# Switch.net
KiCad netlist of a schematic drawn in Altium Designer
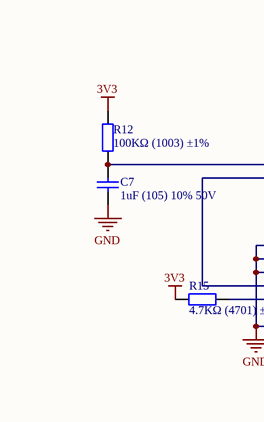
[diagram p0: Switch.SchDoc, top left]
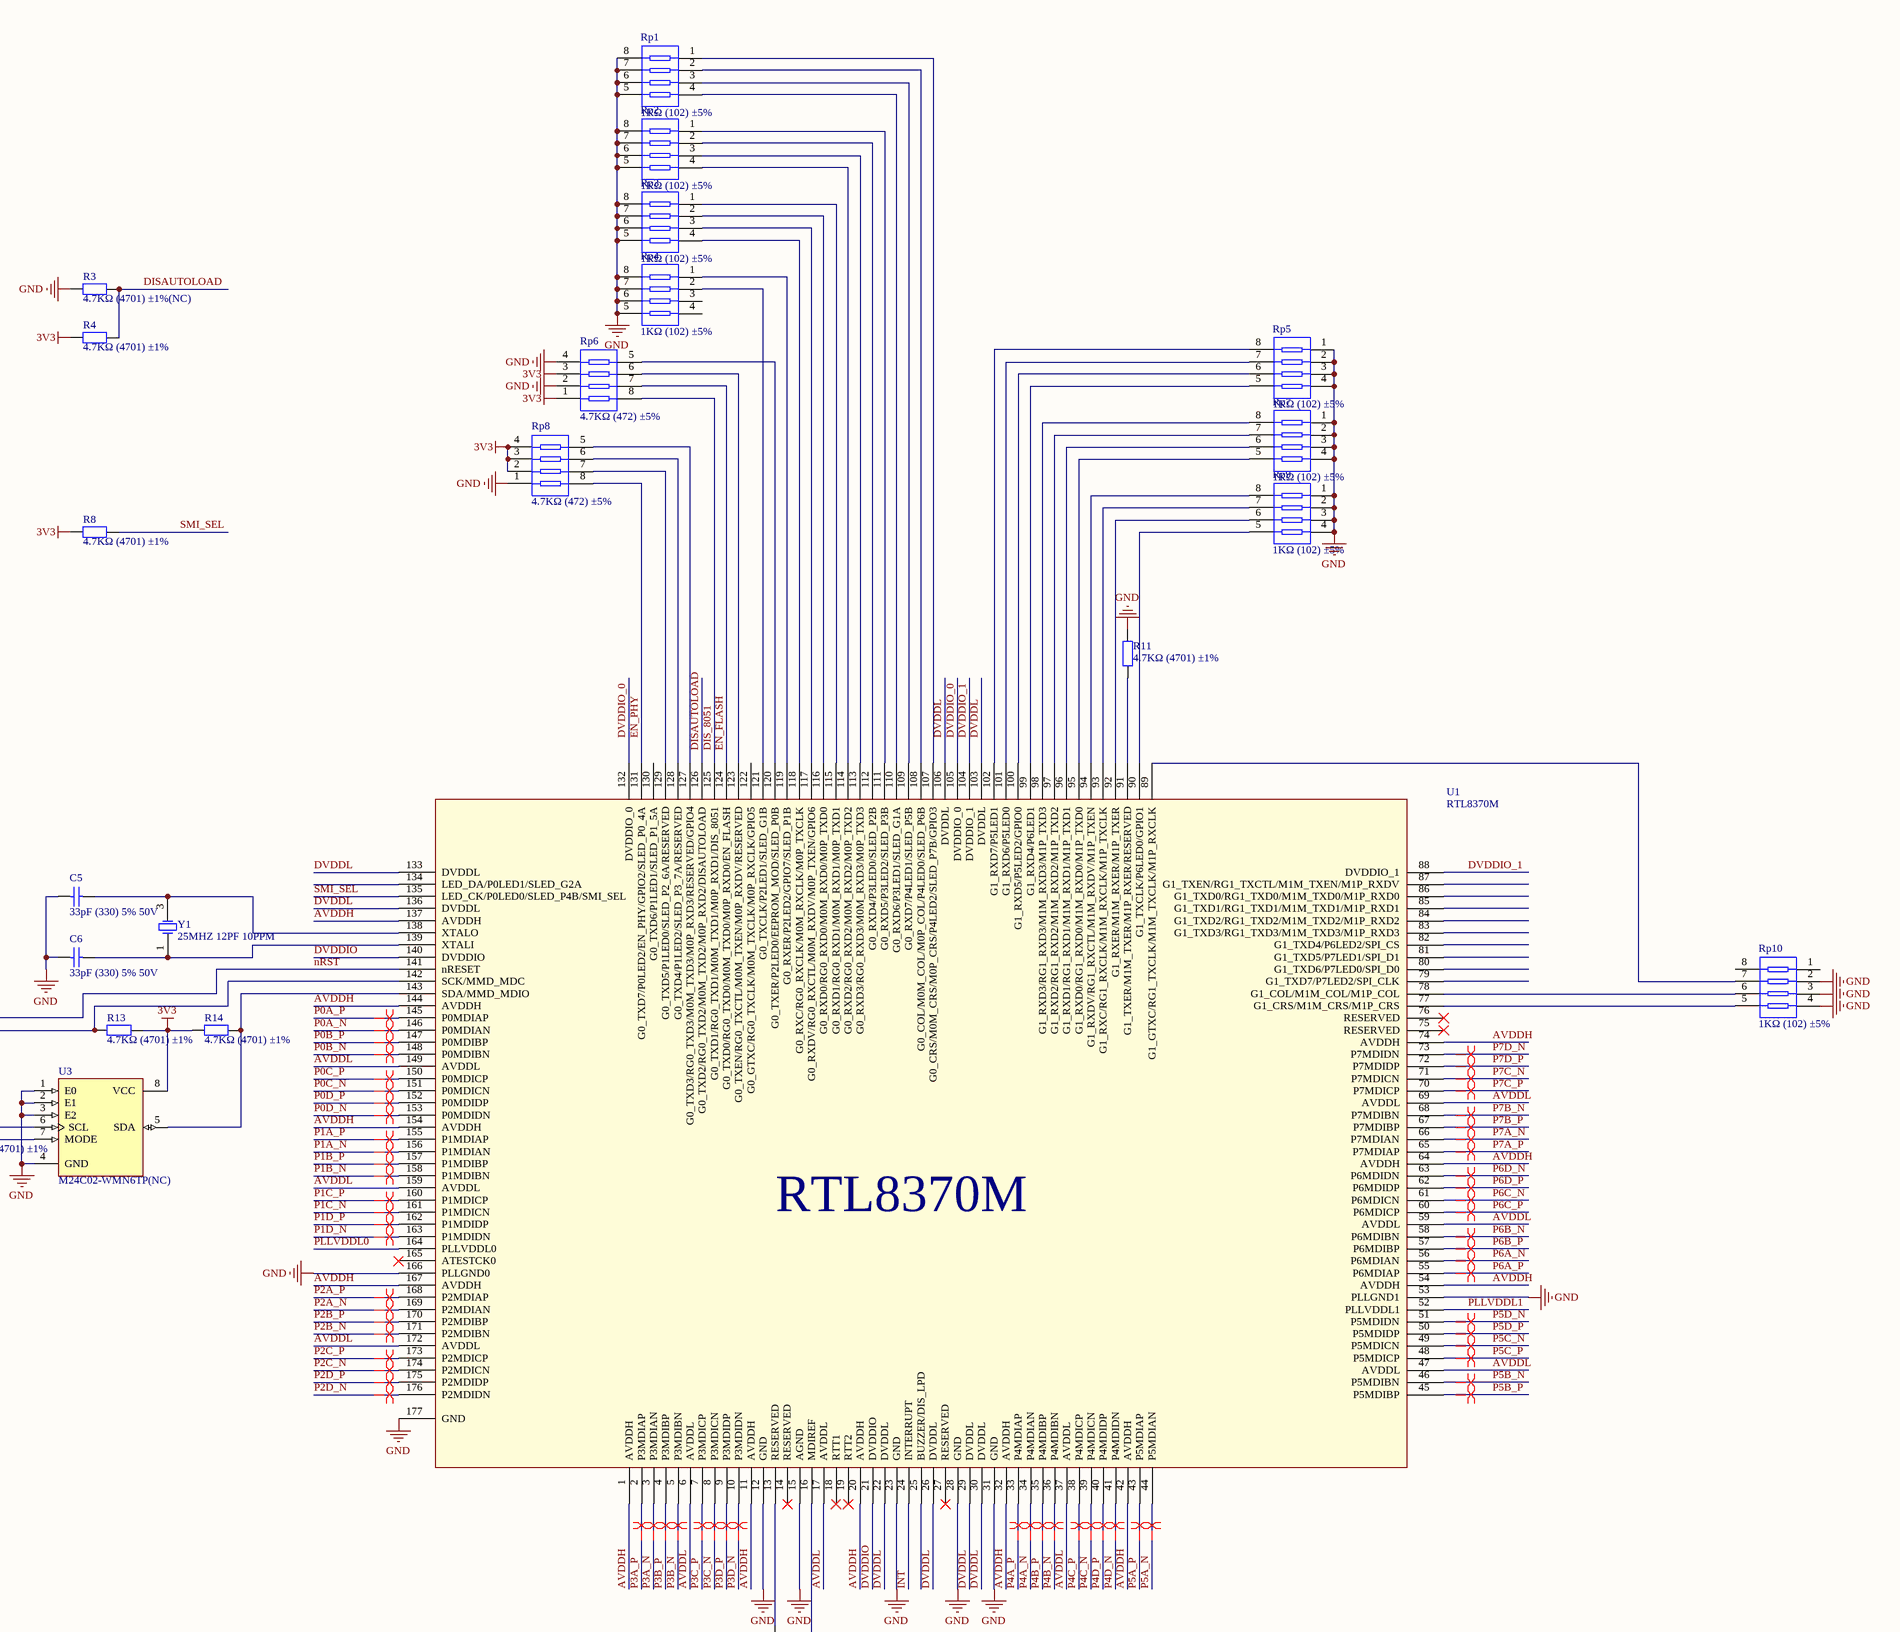
[diagram p1: Switch.SchDoc, top right]
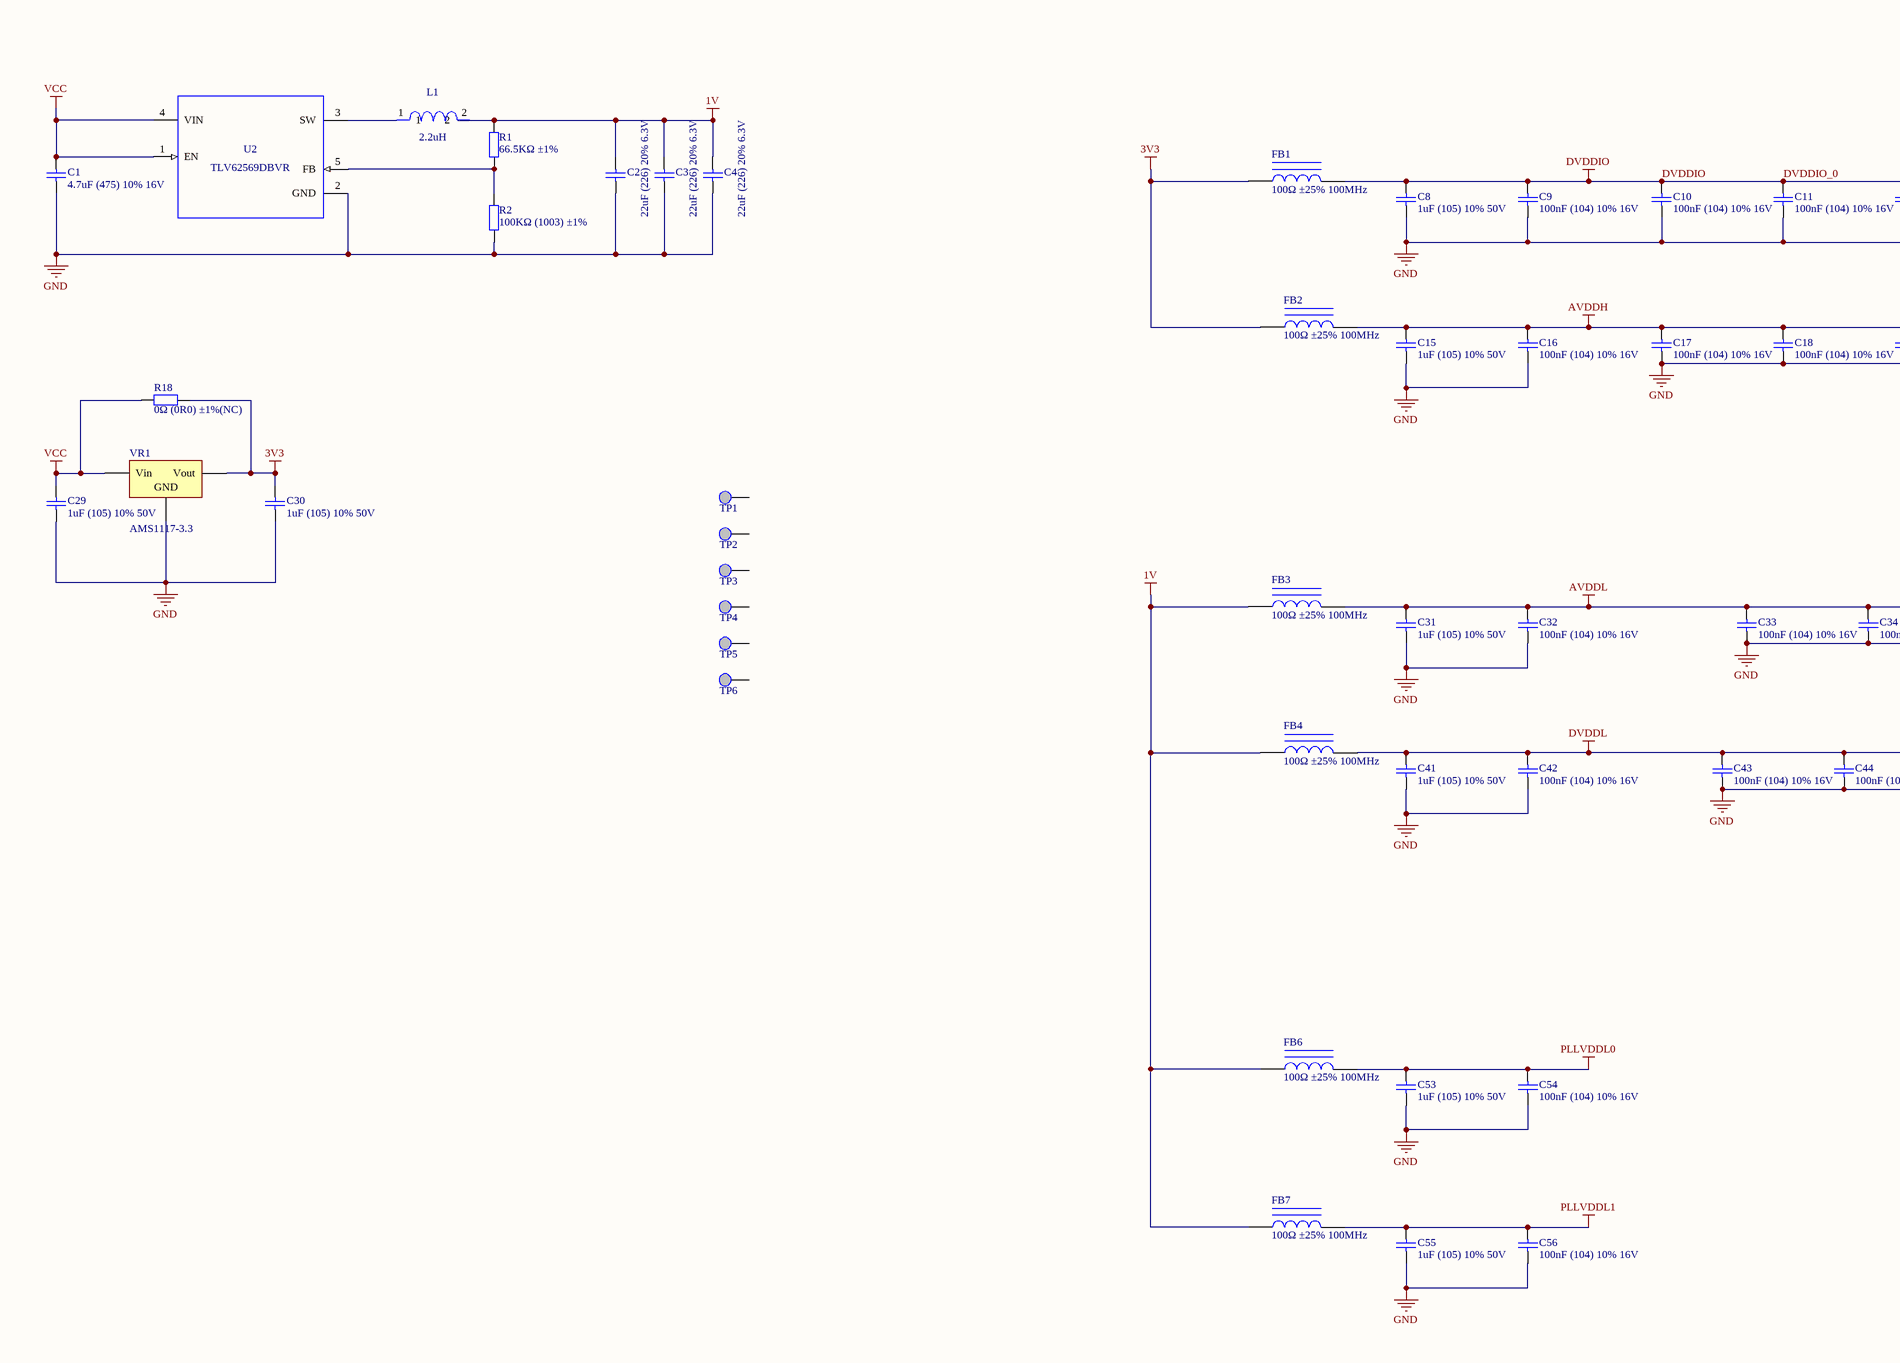
[diagram p2: Switch.SchDoc, bottom left]
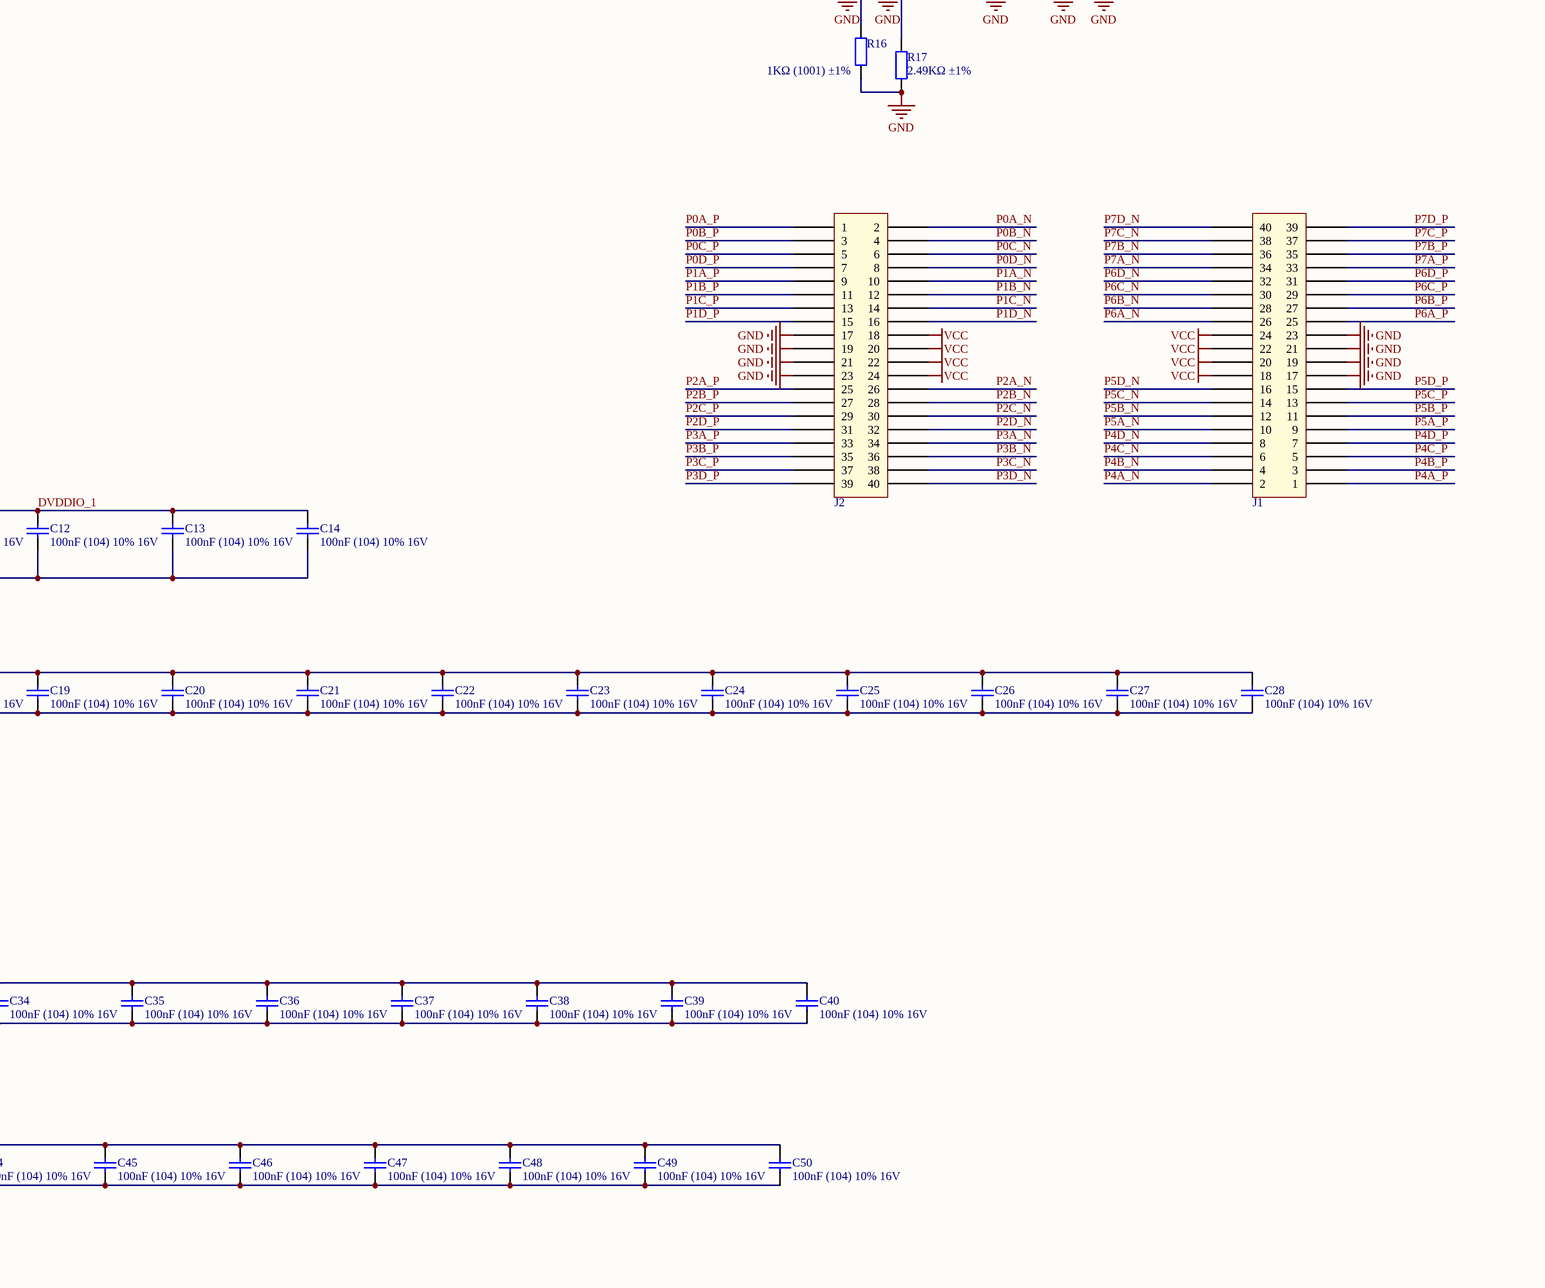
[diagram p3: Switch.SchDoc, bottom right]

(export (version "E")
  (design (tool "Eeschema 10.0.6"))
  (components
    (comp (ref "C1")
      (value "4.7uF (475) 10% 16V")
      (footprint "0603_C")
      (description "贴片电容")
      (libsource (lib "Miscellaneous Devices LC") (part "0603 4.7uF (475) 10% 16V"))
    )
    (comp (ref "C2")
      (value "22uF (226) 20% 6.3V")
      (footprint "0603_C")
      (description "贴片电容")
      (libsource (lib "Miscellaneous Devices LC") (part "0603 22uF (226) 20% 6.3V"))
    )
    (comp (ref "C3")
      (value "22uF (226) 20% 6.3V")
      (footprint "0603_C")
      (description "贴片电容")
      (libsource (lib "Miscellaneous Devices LC") (part "0603 22uF (226) 20% 6.3V"))
    )
    (comp (ref "C4")
      (value "22uF (226) 20% 6.3V")
      (footprint "0603_C")
      (description "贴片电容")
      (libsource (lib "Miscellaneous Devices LC") (part "0603 22uF (226) 20% 6.3V"))
    )
    (comp (ref "C5")
      (value "33pF (330) 5% 50V")
      (footprint "0402_C")
      (description "贴片电容")
      (libsource (lib "Miscellaneous Devices LC") (part "0402 33pF (330) 5% 50V"))
    )
    (comp (ref "C6")
      (value "33pF (330) 5% 50V")
      (footprint "0402_C")
      (description "贴片电容")
      (libsource (lib "Miscellaneous Devices LC") (part "0402 33pF (330) 5% 50V"))
    )
    (comp (ref "C7")
      (value "1uF (105) 10% 50V")
      (footprint "0603_C")
      (description "贴片电容")
      (libsource (lib "Miscellaneous Devices LC") (part "0603 1uF (105) 10% 50V"))
    )
    (comp (ref "C8")
      (value "1uF (105) 10% 50V")
      (footprint "0603_C")
      (description "贴片电容")
      (libsource (lib "Miscellaneous Devices LC") (part "0603 1uF (105) 10% 50V"))
    )
    (comp (ref "C9")
      (value "100nF (104) 10% 16V")
      (footprint "0402_C")
      (description "贴片电容")
      (libsource (lib "Miscellaneous Devices LC") (part "0402 100nF (104) 10% 16V"))
    )
    (comp (ref "C10")
      (value "100nF (104) 10% 16V")
      (footprint "0402_C")
      (description "贴片电容")
      (libsource (lib "Miscellaneous Devices LC") (part "0402 100nF (104) 10% 16V"))
    )
    (comp (ref "C11")
      (value "100nF (104) 10% 16V")
      (footprint "0402_C")
      (description "贴片电容")
      (libsource (lib "Miscellaneous Devices LC") (part "0402 100nF (104) 10% 16V"))
    )
    (comp (ref "C12")
      (value "100nF (104) 10% 16V")
      (footprint "0402_C")
      (description "贴片电容")
      (libsource (lib "Miscellaneous Devices LC") (part "0402 100nF (104) 10% 16V"))
    )
    (comp (ref "C13")
      (value "100nF (104) 10% 16V")
      (footprint "0402_C")
      (description "贴片电容")
      (libsource (lib "Miscellaneous Devices LC") (part "0402 100nF (104) 10% 16V"))
    )
    (comp (ref "C14")
      (value "100nF (104) 10% 16V")
      (footprint "0402_C")
      (description "贴片电容")
      (libsource (lib "Miscellaneous Devices LC") (part "0402 100nF (104) 10% 16V"))
    )
    (comp (ref "C15")
      (value "1uF (105) 10% 50V")
      (footprint "0603_C")
      (description "贴片电容")
      (libsource (lib "Miscellaneous Devices LC") (part "0603 1uF (105) 10% 50V"))
    )
    (comp (ref "C16")
      (value "100nF (104) 10% 16V")
      (footprint "0402_C")
      (description "贴片电容")
      (libsource (lib "Miscellaneous Devices LC") (part "0402 100nF (104) 10% 16V"))
    )
    (comp (ref "C17")
      (value "100nF (104) 10% 16V")
      (footprint "0402_C")
      (description "贴片电容")
      (libsource (lib "Miscellaneous Devices LC") (part "0402 100nF (104) 10% 16V"))
    )
    (comp (ref "C18")
      (value "100nF (104) 10% 16V")
      (footprint "0402_C")
      (description "贴片电容")
      (libsource (lib "Miscellaneous Devices LC") (part "0402 100nF (104) 10% 16V"))
    )
    (comp (ref "C19")
      (value "100nF (104) 10% 16V")
      (footprint "0402_C")
      (description "贴片电容")
      (libsource (lib "Miscellaneous Devices LC") (part "0402 100nF (104) 10% 16V"))
    )
    (comp (ref "C20")
      (value "100nF (104) 10% 16V")
      (footprint "0402_C")
      (description "贴片电容")
      (libsource (lib "Miscellaneous Devices LC") (part "0402 100nF (104) 10% 16V"))
    )
    (comp (ref "C21")
      (value "100nF (104) 10% 16V")
      (footprint "0402_C")
      (description "贴片电容")
      (libsource (lib "Miscellaneous Devices LC") (part "0402 100nF (104) 10% 16V"))
    )
    (comp (ref "C22")
      (value "100nF (104) 10% 16V")
      (footprint "0402_C")
      (description "贴片电容")
      (libsource (lib "Miscellaneous Devices LC") (part "0402 100nF (104) 10% 16V"))
    )
    (comp (ref "C23")
      (value "100nF (104) 10% 16V")
      (footprint "0402_C")
      (description "贴片电容")
      (libsource (lib "Miscellaneous Devices LC") (part "0402 100nF (104) 10% 16V"))
    )
    (comp (ref "C24")
      (value "100nF (104) 10% 16V")
      (footprint "0402_C")
      (description "贴片电容")
      (libsource (lib "Miscellaneous Devices LC") (part "0402 100nF (104) 10% 16V"))
    )
    (comp (ref "C25")
      (value "100nF (104) 10% 16V")
      (footprint "0402_C")
      (description "贴片电容")
      (libsource (lib "Miscellaneous Devices LC") (part "0402 100nF (104) 10% 16V"))
    )
    (comp (ref "C26")
      (value "100nF (104) 10% 16V")
      (footprint "0402_C")
      (description "贴片电容")
      (libsource (lib "Miscellaneous Devices LC") (part "0402 100nF (104) 10% 16V"))
    )
    (comp (ref "C27")
      (value "100nF (104) 10% 16V")
      (footprint "0402_C")
      (description "贴片电容")
      (libsource (lib "Miscellaneous Devices LC") (part "0402 100nF (104) 10% 16V"))
    )
    (comp (ref "C28")
      (value "100nF (104) 10% 16V")
      (footprint "0402_C")
      (description "贴片电容")
      (libsource (lib "Miscellaneous Devices LC") (part "0402 100nF (104) 10% 16V"))
    )
    (comp (ref "C29")
      (value "1uF (105) 10% 50V")
      (footprint "0603_C")
      (description "贴片电容")
      (libsource (lib "Miscellaneous Devices LC") (part "0603 1uF (105) 10% 50V"))
    )
    (comp (ref "C30")
      (value "1uF (105) 10% 50V")
      (footprint "0603_C")
      (description "贴片电容")
      (libsource (lib "Miscellaneous Devices LC") (part "0603 1uF (105) 10% 50V"))
    )
    (comp (ref "C31")
      (value "1uF (105) 10% 50V")
      (footprint "0603_C")
      (description "贴片电容")
      (libsource (lib "Miscellaneous Devices LC") (part "0603 1uF (105) 10% 50V"))
    )
    (comp (ref "C32")
      (value "100nF (104) 10% 16V")
      (footprint "0402_C")
      (description "贴片电容")
      (libsource (lib "Miscellaneous Devices LC") (part "0402 100nF (104) 10% 16V"))
    )
    (comp (ref "C33")
      (value "100nF (104) 10% 16V")
      (footprint "0402_C")
      (description "贴片电容")
      (libsource (lib "Miscellaneous Devices LC") (part "0402 100nF (104) 10% 16V"))
    )
    (comp (ref "C34")
      (value "100nF (104) 10% 16V")
      (footprint "0402_C")
      (description "贴片电容")
      (libsource (lib "Miscellaneous Devices LC") (part "0402 100nF (104) 10% 16V"))
    )
    (comp (ref "C35")
      (value "100nF (104) 10% 16V")
      (footprint "0402_C")
      (description "贴片电容")
      (libsource (lib "Miscellaneous Devices LC") (part "0402 100nF (104) 10% 16V"))
    )
    (comp (ref "C36")
      (value "100nF (104) 10% 16V")
      (footprint "0402_C")
      (description "贴片电容")
      (libsource (lib "Miscellaneous Devices LC") (part "0402 100nF (104) 10% 16V"))
    )
    (comp (ref "C37")
      (value "100nF (104) 10% 16V")
      (footprint "0402_C")
      (description "贴片电容")
      (libsource (lib "Miscellaneous Devices LC") (part "0402 100nF (104) 10% 16V"))
    )
    (comp (ref "C38")
      (value "100nF (104) 10% 16V")
      (footprint "0402_C")
      (description "贴片电容")
      (libsource (lib "Miscellaneous Devices LC") (part "0402 100nF (104) 10% 16V"))
    )
    (comp (ref "C39")
      (value "100nF (104) 10% 16V")
      (footprint "0402_C")
      (description "贴片电容")
      (libsource (lib "Miscellaneous Devices LC") (part "0402 100nF (104) 10% 16V"))
    )
    (comp (ref "C40")
      (value "100nF (104) 10% 16V")
      (footprint "0402_C")
      (description "贴片电容")
      (libsource (lib "Miscellaneous Devices LC") (part "0402 100nF (104) 10% 16V"))
    )
    (comp (ref "C41")
      (value "1uF (105) 10% 50V")
      (footprint "0603_C")
      (description "贴片电容")
      (libsource (lib "Miscellaneous Devices LC") (part "0603 1uF (105) 10% 50V"))
    )
    (comp (ref "C42")
      (value "100nF (104) 10% 16V")
      (footprint "0402_C")
      (description "贴片电容")
      (libsource (lib "Miscellaneous Devices LC") (part "0402 100nF (104) 10% 16V"))
    )
    (comp (ref "C43")
      (value "100nF (104) 10% 16V")
      (footprint "0402_C")
      (description "贴片电容")
      (libsource (lib "Miscellaneous Devices LC") (part "0402 100nF (104) 10% 16V"))
    )
    (comp (ref "C44")
      (value "100nF (104) 10% 16V")
      (footprint "0402_C")
      (description "贴片电容")
      (libsource (lib "Miscellaneous Devices LC") (part "0402 100nF (104) 10% 16V"))
    )
    (comp (ref "C45")
      (value "100nF (104) 10% 16V")
      (footprint "0402_C")
      (description "贴片电容")
      (libsource (lib "Miscellaneous Devices LC") (part "0402 100nF (104) 10% 16V"))
    )
    (comp (ref "C46")
      (value "100nF (104) 10% 16V")
      (footprint "0402_C")
      (description "贴片电容")
      (libsource (lib "Miscellaneous Devices LC") (part "0402 100nF (104) 10% 16V"))
    )
    (comp (ref "C47")
      (value "100nF (104) 10% 16V")
      (footprint "0402_C")
      (description "贴片电容")
      (libsource (lib "Miscellaneous Devices LC") (part "0402 100nF (104) 10% 16V"))
    )
    (comp (ref "C48")
      (value "100nF (104) 10% 16V")
      (footprint "0402_C")
      (description "贴片电容")
      (libsource (lib "Miscellaneous Devices LC") (part "0402 100nF (104) 10% 16V"))
    )
    (comp (ref "C49")
      (value "100nF (104) 10% 16V")
      (footprint "0402_C")
      (description "贴片电容")
      (libsource (lib "Miscellaneous Devices LC") (part "0402 100nF (104) 10% 16V"))
    )
    (comp (ref "C50")
      (value "100nF (104) 10% 16V")
      (footprint "0402_C")
      (description "贴片电容")
      (libsource (lib "Miscellaneous Devices LC") (part "0402 100nF (104) 10% 16V"))
    )
    (comp (ref "C53")
      (value "1uF (105) 10% 50V")
      (footprint "0603_C")
      (description "贴片电容")
      (libsource (lib "Miscellaneous Devices LC") (part "0603 1uF (105) 10% 50V"))
    )
    (comp (ref "C54")
      (value "100nF (104) 10% 16V")
      (footprint "0402_C")
      (description "贴片电容")
      (libsource (lib "Miscellaneous Devices LC") (part "0402 100nF (104) 10% 16V"))
    )
    (comp (ref "C55")
      (value "1uF (105) 10% 50V")
      (footprint "0603_C")
      (description "贴片电容")
      (libsource (lib "Miscellaneous Devices LC") (part "0603 1uF (105) 10% 50V"))
    )
    (comp (ref "C56")
      (value "100nF (104) 10% 16V")
      (footprint "0402_C")
      (description "贴片电容")
      (libsource (lib "Miscellaneous Devices LC") (part "0402 100nF (104) 10% 16V"))
    )
    (comp (ref "FB1")
      (value "100Ω ±25% 100MHz")
      (footprint "0805_L")
      (description "贴片磁珠")
      (libsource (lib "Miscellaneous Devices LC") (part "0805 100Ω 25% 100MHz"))
    )
    (comp (ref "FB2")
      (value "100Ω ±25% 100MHz")
      (footprint "0805_L")
      (description "贴片磁珠")
      (libsource (lib "Miscellaneous Devices LC") (part "0805 100Ω 25% 100MHz"))
    )
    (comp (ref "FB3")
      (value "100Ω ±25% 100MHz")
      (footprint "0805_L")
      (description "贴片磁珠")
      (libsource (lib "Miscellaneous Devices LC") (part "0805 100Ω 25% 100MHz"))
    )
    (comp (ref "FB4")
      (value "100Ω ±25% 100MHz")
      (footprint "0805_L")
      (description "贴片磁珠")
      (libsource (lib "Miscellaneous Devices LC") (part "0805 100Ω 25% 100MHz"))
    )
    (comp (ref "FB6")
      (value "100Ω ±25% 100MHz")
      (footprint "0805_L")
      (description "贴片磁珠")
      (libsource (lib "Miscellaneous Devices LC") (part "0805 100Ω 25% 100MHz"))
    )
    (comp (ref "FB7")
      (value "100Ω ±25% 100MHz")
      (footprint "0805_L")
      (description "贴片磁珠")
      (libsource (lib "Miscellaneous Devices LC") (part "0805 100Ω 25% 100MHz"))
    )
    (comp (ref "J1")
      (value "Header20x2_2.54_female")
      (footprint "2-534206-0")
      (libsource (lib "") (part "Header20x2_2.54_female_1"))
    )
    (comp (ref "J2")
      (value "Header20x2_2.54_female")
      (footprint "2-534206-0")
      (libsource (lib "Lib") (part "Header20x2_2.54_female"))
    )
    (comp (ref "L1")
      (value "2.2uH")
      (footprint "XAL4020")
      (description "XAL4020-222MEB")
      (libsource (lib "TI WEBENCH") (part "L1"))
    )
    (comp (ref "R1")
      (value "66.5KΩ ±1%")
      (footprint "0603_R")
      (description "贴片电阻")
      (libsource (lib "Miscellaneous Devices LC") (part "0603 100KΩ (1003) 1%"))
    )
    (comp (ref "R2")
      (value "100KΩ (1003) ±1%")
      (footprint "0603_R")
      (description "贴片电阻")
      (libsource (lib "Miscellaneous Devices LC") (part "0603 100KΩ (1003) 1%"))
    )
    (comp (ref "R3")
      (value "4.7KΩ (4701) ±1%(NC)")
      (footprint "0402_R")
      (description "贴片电阻")
      (libsource (lib "Miscellaneous Devices LC") (part "0402 4.7KΩ (4701) 1%"))
    )
    (comp (ref "R4")
      (value "4.7KΩ (4701) ±1%")
      (footprint "0402_R")
      (description "贴片电阻")
      (libsource (lib "Miscellaneous Devices LC") (part "0402 4.7KΩ (4701) 1%"))
    )
    (comp (ref "R8")
      (value "4.7KΩ (4701) ±1%")
      (footprint "0402_R")
      (description "贴片电阻")
      (libsource (lib "Miscellaneous Devices LC") (part "0402 4.7KΩ (4701) 1%"))
    )
    (comp (ref "R11")
      (value "4.7KΩ (4701) ±1%")
      (footprint "0402_R")
      (description "贴片电阻")
      (libsource (lib "") (part "0402 4.7KΩ (4701) 1%_1"))
    )
    (comp (ref "R12")
      (value "100KΩ (1003) ±1%")
      (footprint "0402_R")
      (description "贴片电阻")
      (libsource (lib "Miscellaneous Devices LC") (part "0402 100KΩ (1003) 1%"))
    )
    (comp (ref "R13")
      (value "4.7KΩ (4701) ±1%")
      (footprint "0402_R")
      (description "贴片电阻")
      (libsource (lib "Miscellaneous Devices LC") (part "0402 4.7KΩ (4701) 1%"))
    )
    (comp (ref "R14")
      (value "4.7KΩ (4701) ±1%")
      (footprint "0402_R")
      (description "贴片电阻")
      (libsource (lib "Miscellaneous Devices LC") (part "0402 4.7KΩ (4701) 1%"))
    )
    (comp (ref "R15")
      (value "4.7KΩ (4701) ±1%")
      (footprint "0402_R")
      (description "贴片电阻")
      (libsource (lib "Miscellaneous Devices LC") (part "0402 4.7KΩ (4701) 1%"))
    )
    (comp (ref "R16")
      (value "1KΩ (1001) ±1%")
      (footprint "0402_R")
      (description "贴片电阻")
      (libsource (lib "Miscellaneous Devices LC") (part "0402 1KΩ (1001) 1%"))
    )
    (comp (ref "R17")
      (value "2.49KΩ ±1%")
      (footprint "0402_R")
      (description "贴片电阻")
      (libsource (lib "Miscellaneous Devices LC") (part "0402 2KΩ (2001) 1%"))
    )
    (comp (ref "R18")
      (value "0Ω (0R0) ±1%(NC)")
      (footprint "1206_R")
      (description "贴片电阻")
      (libsource (lib "Miscellaneous Devices LC") (part "1206 0Ω (0R0) 1%"))
    )
    (comp (ref "Rp1")
      (value "1KΩ (102) ±5%")
      (footprint "0402_Rx4")
      (description "贴片排阻")
      (libsource (lib "Miscellaneous Devices LC") (part "0402*4 1KΩ (102) 5%"))
    )
    (comp (ref "Rp2")
      (value "1KΩ (102) ±5%")
      (footprint "0402_Rx4")
      (description "贴片排阻")
      (libsource (lib "Miscellaneous Devices LC") (part "0402*4 1KΩ (102) 5%"))
    )
    (comp (ref "Rp3")
      (value "1KΩ (102) ±5%")
      (footprint "0402_Rx4")
      (description "贴片排阻")
      (libsource (lib "Miscellaneous Devices LC") (part "0402*4 1KΩ (102) 5%"))
    )
    (comp (ref "Rp4")
      (value "1KΩ (102) ±5%")
      (footprint "0402_Rx4")
      (description "贴片排阻")
      (libsource (lib "Miscellaneous Devices LC") (part "0402*4 1KΩ (102) 5%"))
    )
    (comp (ref "Rp5")
      (value "1KΩ (102) ±5%")
      (footprint "0402_Rx4")
      (description "贴片排阻")
      (libsource (lib "Miscellaneous Devices LC") (part "0402*4 1KΩ (102) 5%"))
    )
    (comp (ref "Rp6")
      (value "4.7KΩ (472) ±5%")
      (footprint "0603_Rx4")
      (description "贴片排阻")
      (libsource (lib "Miscellaneous Devices LC") (part "0603*4  4.7KΩ (472) 5%"))
    )
    (comp (ref "Rp7")
      (value "1KΩ (102) ±5%")
      (footprint "0402_Rx4")
      (description "贴片排阻")
      (libsource (lib "Miscellaneous Devices LC") (part "0402*4 1KΩ (102) 5%"))
    )
    (comp (ref "Rp8")
      (value "4.7KΩ (472) ±5%")
      (footprint "0603_Rx4")
      (description "贴片排阻")
      (libsource (lib "Miscellaneous Devices LC") (part "0603*4  4.7KΩ (472) 5%"))
    )
    (comp (ref "Rp9")
      (value "1KΩ (102) ±5%")
      (footprint "0402_Rx4")
      (description "贴片排阻")
      (libsource (lib "Miscellaneous Devices LC") (part "0402*4 1KΩ (102) 5%"))
    )
    (comp (ref "Rp10")
      (value "1KΩ (102) ±5%")
      (footprint "0402_Rx4")
      (description "贴片排阻")
      (libsource (lib "Miscellaneous Devices LC") (part "0402*4 1KΩ (102) 5%"))
    )
    (comp (ref "TP1")
      (value "Test Point, 30mil")
      (footprint "test_point_30_mil")
      (libsource (lib "RoboteX") (part "test_point"))
    )
    (comp (ref "TP2")
      (value "Test Point, 30mil")
      (footprint "test_point_30_mil")
      (libsource (lib "RoboteX") (part "test_point"))
    )
    (comp (ref "TP3")
      (value "Test Point, 30mil")
      (footprint "test_point_30_mil")
      (libsource (lib "RoboteX") (part "test_point"))
    )
    (comp (ref "TP4")
      (value "Test Point, 30mil")
      (footprint "test_point_30_mil")
      (libsource (lib "RoboteX") (part "test_point"))
    )
    (comp (ref "TP5")
      (value "Test Point, 30mil")
      (footprint "test_point_30_mil")
      (libsource (lib "RoboteX") (part "test_point"))
    )
    (comp (ref "TP6")
      (value "Test Point, 30mil")
      (footprint "test_point_30_mil")
      (libsource (lib "RoboteX") (part "test_point"))
    )
    (comp (ref "U1")
      (value "RTL8370M")
      (footprint "PLQP0176LA-B-M")
      (libsource (lib "Lib") (part "RTL8370M"))
    )
    (comp (ref "U2")
      (value "TLV62569DBVR")
      (footprint "DBV0005A_M")
      (fields (field (name "PACKAGEREFERENCE") "TLV62569DBVR"))
      (libsource (lib "TI WEBENCH") (part "U1"))
    )
    (comp (ref "U3")
      (value "M24C02-WMN6TP(NC)")
      (footprint "SOIC-8_150mil")
      (description "EEPROM")
      (libsource (lib "Miscellaneous Devices LC") (part "M24C02-WMN6TP_[C7562]"))
    )
    (comp (ref "VR1")
      (value "AMS1117-3.3")
      (footprint "SOT-223")
      (description "低压差线性稳压(LDO)")
      (libsource (lib "Miscellaneous Devices LC") (part "SOT-223 AMS1117-3.3"))
    )
    (comp (ref "Y1")
      (value "25MHZ 12PF 10PPM")
      (footprint "SMD-3225_4P")
      (description "贴片晶振")
      (libsource (lib "Miscellaneous Devices LC") (part "SMD-3225_4P  25MHZ 12PF 10PPM"))
    )
  )
  (nets
    (net (code "1") (name "/DISAUTOLOAD") (class "Default")
      (node (ref "R3") (pin "2") (pinfunction "2_2") (pintype "passive"))
      (node (ref "R4") (pin "2") (pinfunction "2_2") (pintype "passive"))
      (node (ref "U1") (pin "126") (pinfunction "G0_TXD2/RG0_TXD2/M0M_TXD2/M0P_RXD2/DISAUTOLOAD_126") (pintype "passive"))
    )
    (net (code "2") (name "/DIS_8051") (class "Default")
      (node (ref "Rp6") (pin "8") (pinfunction "8_8") (pintype "passive"))
      (node (ref "U1") (pin "125") (pinfunction "G0_TXD1/RG0_TXD1/M0M_TXD1/M0P_RXD1/DIS_8051_125") (pintype "passive"))
    )
    (net (code "3") (name "/EN_FLASH") (class "Default")
      (node (ref "Rp6") (pin "7") (pinfunction "7_7") (pintype "passive"))
      (node (ref "U1") (pin "124") (pinfunction "G0_TXD0/RG0_TXD0/M0M_TXD0/M0P_RXD0/EN_FLASH_124") (pintype "passive"))
    )
    (net (code "4") (name "/EN_PHY") (class "Default")
      (node (ref "Rp8") (pin "8") (pinfunction "8_8") (pintype "passive"))
      (node (ref "U1") (pin "131") (pinfunction "G0_TXD7/P0LED2/EN_PHY/GPIO2/SLED_P0_4A_131") (pintype "passive"))
    )
    (net (code "5") (name "/INT") (class "Default")
      (node (ref "U1") (pin "24") (pinfunction "INTERRUPT_24") (pintype "passive"))
    )
    (net (code "6") (name "/P0A_N") (class "Default")
      (node (ref "J2") (pin "2") (pinfunction "2_2") (pintype "passive"))
      (node (ref "U1") (pin "146") (pinfunction "P0MDIAN_146") (pintype "passive"))
    )
    (net (code "7") (name "/P0A_P") (class "Default")
      (node (ref "J2") (pin "1") (pinfunction "1_1") (pintype "passive"))
      (node (ref "U1") (pin "145") (pinfunction "P0MDIAP_145") (pintype "passive"))
    )
    (net (code "8") (name "/P0B_N") (class "Default")
      (node (ref "J2") (pin "4") (pinfunction "4_4") (pintype "passive"))
      (node (ref "U1") (pin "148") (pinfunction "P0MDIBN_148") (pintype "passive"))
    )
    (net (code "9") (name "/P0B_P") (class "Default")
      (node (ref "J2") (pin "3") (pinfunction "3_3") (pintype "passive"))
      (node (ref "U1") (pin "147") (pinfunction "P0MDIBP_147") (pintype "passive"))
    )
    (net (code "10") (name "/P0C_N") (class "Default")
      (node (ref "J2") (pin "6") (pinfunction "6_6") (pintype "passive"))
      (node (ref "U1") (pin "151") (pinfunction "P0MDICN_151") (pintype "passive"))
    )
    (net (code "11") (name "/P0C_P") (class "Default")
      (node (ref "J2") (pin "5") (pinfunction "5_5") (pintype "passive"))
      (node (ref "U1") (pin "150") (pinfunction "P0MDICP_150") (pintype "passive"))
    )
    (net (code "12") (name "/P0D_N") (class "Default")
      (node (ref "J2") (pin "8") (pinfunction "8_8") (pintype "passive"))
      (node (ref "U1") (pin "153") (pinfunction "P0MDIDN_153") (pintype "passive"))
    )
    (net (code "13") (name "/P0D_P") (class "Default")
      (node (ref "J2") (pin "7") (pinfunction "7_7") (pintype "passive"))
      (node (ref "U1") (pin "152") (pinfunction "P0MDIDP_152") (pintype "passive"))
    )
    (net (code "14") (name "/P1A_N") (class "Default")
      (node (ref "J2") (pin "10") (pinfunction "10_10") (pintype "passive"))
      (node (ref "U1") (pin "156") (pinfunction "P1MDIAN_156") (pintype "passive"))
    )
    (net (code "15") (name "/P1A_P") (class "Default")
      (node (ref "J2") (pin "9") (pinfunction "9_9") (pintype "passive"))
      (node (ref "U1") (pin "155") (pinfunction "P1MDIAP_155") (pintype "passive"))
    )
    (net (code "16") (name "/P1B_N") (class "Default")
      (node (ref "J2") (pin "12") (pinfunction "12_12") (pintype "passive"))
      (node (ref "U1") (pin "158") (pinfunction "P1MDIBN_158") (pintype "passive"))
    )
    (net (code "17") (name "/P1B_P") (class "Default")
      (node (ref "J2") (pin "11") (pinfunction "11_11") (pintype "passive"))
      (node (ref "U1") (pin "157") (pinfunction "P1MDIBP_157") (pintype "passive"))
    )
    (net (code "18") (name "/P1C_N") (class "Default")
      (node (ref "J2") (pin "14") (pinfunction "14_14") (pintype "passive"))
      (node (ref "U1") (pin "161") (pinfunction "P1MDICN_161") (pintype "passive"))
    )
    (net (code "19") (name "/P1C_P") (class "Default")
      (node (ref "J2") (pin "13") (pinfunction "13_13") (pintype "passive"))
      (node (ref "U1") (pin "160") (pinfunction "P1MDICP_160") (pintype "passive"))
    )
    (net (code "20") (name "/P1D_N") (class "Default")
      (node (ref "J2") (pin "16") (pinfunction "16_16") (pintype "passive"))
      (node (ref "U1") (pin "163") (pinfunction "P1MDIDN_163") (pintype "passive"))
    )
    (net (code "21") (name "/P1D_P") (class "Default")
      (node (ref "J2") (pin "15") (pinfunction "15_15") (pintype "passive"))
      (node (ref "U1") (pin "162") (pinfunction "P1MDIDP_162") (pintype "passive"))
    )
    (net (code "22") (name "/P2A_N") (class "Default")
      (node (ref "J2") (pin "26") (pinfunction "26_26") (pintype "passive"))
      (node (ref "U1") (pin "169") (pinfunction "P2MDIAN_169") (pintype "passive"))
    )
    (net (code "23") (name "/P2A_P") (class "Default")
      (node (ref "J2") (pin "25") (pinfunction "25_25") (pintype "passive"))
      (node (ref "U1") (pin "168") (pinfunction "P2MDIAP_168") (pintype "passive"))
    )
    (net (code "24") (name "/P2B_N") (class "Default")
      (node (ref "J2") (pin "28") (pinfunction "28_28") (pintype "passive"))
      (node (ref "U1") (pin "171") (pinfunction "P2MDIBN_171") (pintype "passive"))
    )
    (net (code "25") (name "/P2B_P") (class "Default")
      (node (ref "J2") (pin "27") (pinfunction "27_27") (pintype "passive"))
      (node (ref "U1") (pin "170") (pinfunction "P2MDIBP_170") (pintype "passive"))
    )
    (net (code "26") (name "/P2C_N") (class "Default")
      (node (ref "J2") (pin "30") (pinfunction "30_30") (pintype "passive"))
      (node (ref "U1") (pin "174") (pinfunction "P2MDICN_174") (pintype "passive"))
    )
    (net (code "27") (name "/P2C_P") (class "Default")
      (node (ref "J2") (pin "29") (pinfunction "29_29") (pintype "passive"))
      (node (ref "U1") (pin "173") (pinfunction "P2MDICP_173") (pintype "passive"))
    )
    (net (code "28") (name "/P2D_N") (class "Default")
      (node (ref "J2") (pin "32") (pinfunction "32_32") (pintype "passive"))
      (node (ref "U1") (pin "176") (pinfunction "P2MDIDN_176") (pintype "passive"))
    )
    (net (code "29") (name "/P2D_P") (class "Default")
      (node (ref "J2") (pin "31") (pinfunction "31_31") (pintype "passive"))
      (node (ref "U1") (pin "175") (pinfunction "P2MDIDP_175") (pintype "passive"))
    )
    (net (code "30") (name "/P3A_N") (class "Default")
      (node (ref "J2") (pin "34") (pinfunction "34_34") (pintype "passive"))
      (node (ref "U1") (pin "3") (pinfunction "P3MDIAN_3") (pintype "passive"))
    )
    (net (code "31") (name "/P3A_P") (class "Default")
      (node (ref "J2") (pin "33") (pinfunction "33_33") (pintype "passive"))
      (node (ref "U1") (pin "2") (pinfunction "P3MDIAP_2") (pintype "passive"))
    )
    (net (code "32") (name "/P3B_N") (class "Default")
      (node (ref "J2") (pin "36") (pinfunction "36_36") (pintype "passive"))
      (node (ref "U1") (pin "5") (pinfunction "P3MDIBN_5") (pintype "passive"))
    )
    (net (code "33") (name "/P3B_P") (class "Default")
      (node (ref "J2") (pin "35") (pinfunction "35_35") (pintype "passive"))
      (node (ref "U1") (pin "4") (pinfunction "P3MDIBP_4") (pintype "passive"))
    )
    (net (code "34") (name "/P3C_N") (class "Default")
      (node (ref "J2") (pin "38") (pinfunction "38_38") (pintype "passive"))
      (node (ref "U1") (pin "8") (pinfunction "P3MDICN_8") (pintype "passive"))
    )
    (net (code "35") (name "/P3C_P") (class "Default")
      (node (ref "J2") (pin "37") (pinfunction "37_37") (pintype "passive"))
      (node (ref "U1") (pin "7") (pinfunction "P3MDICP_7") (pintype "passive"))
    )
    (net (code "36") (name "/P3D_N") (class "Default")
      (node (ref "J2") (pin "40") (pinfunction "40_40") (pintype "passive"))
      (node (ref "U1") (pin "10") (pinfunction "P3MDIDN_10") (pintype "passive"))
    )
    (net (code "37") (name "/P3D_P") (class "Default")
      (node (ref "J2") (pin "39") (pinfunction "39_39") (pintype "passive"))
      (node (ref "U1") (pin "9") (pinfunction "P3MDIDP_9") (pintype "passive"))
    )
    (net (code "38") (name "/P4A_N") (class "Default")
      (node (ref "J1") (pin "2") (pinfunction "2_2") (pintype "passive"))
      (node (ref "U1") (pin "34") (pinfunction "P4MDIAN_34") (pintype "passive"))
    )
    (net (code "39") (name "/P4A_P") (class "Default")
      (node (ref "J1") (pin "1") (pinfunction "1_1") (pintype "passive"))
      (node (ref "U1") (pin "33") (pinfunction "P4MDIAP_33") (pintype "passive"))
    )
    (net (code "40") (name "/P4B_N") (class "Default")
      (node (ref "J1") (pin "4") (pinfunction "4_4") (pintype "passive"))
      (node (ref "U1") (pin "36") (pinfunction "P4MDIBN_36") (pintype "passive"))
    )
    (net (code "41") (name "/P4B_P") (class "Default")
      (node (ref "J1") (pin "3") (pinfunction "3_3") (pintype "passive"))
      (node (ref "U1") (pin "35") (pinfunction "P4MDIBP_35") (pintype "passive"))
    )
    (net (code "42") (name "/P4C_N") (class "Default")
      (node (ref "J1") (pin "6") (pinfunction "6_6") (pintype "passive"))
      (node (ref "U1") (pin "39") (pinfunction "P4MDICN_39") (pintype "passive"))
    )
    (net (code "43") (name "/P4C_P") (class "Default")
      (node (ref "J1") (pin "5") (pinfunction "5_5") (pintype "passive"))
      (node (ref "U1") (pin "38") (pinfunction "P4MDICP_38") (pintype "passive"))
    )
    (net (code "44") (name "/P4D_N") (class "Default")
      (node (ref "J1") (pin "8") (pinfunction "8_8") (pintype "passive"))
      (node (ref "U1") (pin "41") (pinfunction "P4MDIDN_41") (pintype "passive"))
    )
    (net (code "45") (name "/P4D_P") (class "Default")
      (node (ref "J1") (pin "7") (pinfunction "7_7") (pintype "passive"))
      (node (ref "U1") (pin "40") (pinfunction "P4MDIDP_40") (pintype "passive"))
    )
    (net (code "46") (name "/P5A_N") (class "Default")
      (node (ref "J1") (pin "10") (pinfunction "10_10") (pintype "passive"))
      (node (ref "U1") (pin "44") (pinfunction "P5MDIAN_44") (pintype "passive"))
    )
    (net (code "47") (name "/P5A_P") (class "Default")
      (node (ref "J1") (pin "9") (pinfunction "9_9") (pintype "passive"))
      (node (ref "U1") (pin "43") (pinfunction "P5MDIAP_43") (pintype "passive"))
    )
    (net (code "48") (name "/P5B_N") (class "Default")
      (node (ref "J1") (pin "12") (pinfunction "12_12") (pintype "passive"))
      (node (ref "U1") (pin "46") (pinfunction "P5MDIBN_46") (pintype "passive"))
    )
    (net (code "49") (name "/P5B_P") (class "Default")
      (node (ref "J1") (pin "11") (pinfunction "11_11") (pintype "passive"))
      (node (ref "U1") (pin "45") (pinfunction "P5MDIBP_45") (pintype "passive"))
    )
    (net (code "50") (name "/P5C_N") (class "Default")
      (node (ref "J1") (pin "14") (pinfunction "14_14") (pintype "passive"))
      (node (ref "U1") (pin "49") (pinfunction "P5MDICN_49") (pintype "passive"))
    )
    (net (code "51") (name "/P5C_P") (class "Default")
      (node (ref "J1") (pin "13") (pinfunction "13_13") (pintype "passive"))
      (node (ref "U1") (pin "48") (pinfunction "P5MDICP_48") (pintype "passive"))
    )
    (net (code "52") (name "/P5D_N") (class "Default")
      (node (ref "J1") (pin "16") (pinfunction "16_16") (pintype "passive"))
      (node (ref "U1") (pin "51") (pinfunction "P5MDIDN_51") (pintype "passive"))
    )
    (net (code "53") (name "/P5D_P") (class "Default")
      (node (ref "J1") (pin "15") (pinfunction "15_15") (pintype "passive"))
      (node (ref "U1") (pin "50") (pinfunction "P5MDIDP_50") (pintype "passive"))
    )
    (net (code "54") (name "/P6A_N") (class "Default")
      (node (ref "J1") (pin "26") (pinfunction "26_26") (pintype "passive"))
      (node (ref "U1") (pin "56") (pinfunction "P6MDIAN_56") (pintype "passive"))
    )
    (net (code "55") (name "/P6A_P") (class "Default")
      (node (ref "J1") (pin "25") (pinfunction "25_25") (pintype "passive"))
      (node (ref "U1") (pin "55") (pinfunction "P6MDIAP_55") (pintype "passive"))
    )
    (net (code "56") (name "/P6B_N") (class "Default")
      (node (ref "J1") (pin "28") (pinfunction "28_28") (pintype "passive"))
      (node (ref "U1") (pin "58") (pinfunction "P6MDIBN_58") (pintype "passive"))
    )
    (net (code "57") (name "/P6B_P") (class "Default")
      (node (ref "J1") (pin "27") (pinfunction "27_27") (pintype "passive"))
      (node (ref "U1") (pin "57") (pinfunction "P6MDIBP_57") (pintype "passive"))
    )
    (net (code "58") (name "/P6C_N") (class "Default")
      (node (ref "J1") (pin "30") (pinfunction "30_30") (pintype "passive"))
      (node (ref "U1") (pin "61") (pinfunction "P6MDICN_61") (pintype "passive"))
    )
    (net (code "59") (name "/P6C_P") (class "Default")
      (node (ref "J1") (pin "29") (pinfunction "29_29") (pintype "passive"))
      (node (ref "U1") (pin "60") (pinfunction "P6MDICP_60") (pintype "passive"))
    )
    (net (code "60") (name "/P6D_N") (class "Default")
      (node (ref "J1") (pin "32") (pinfunction "32_32") (pintype "passive"))
      (node (ref "U1") (pin "63") (pinfunction "P6MDIDN_63") (pintype "passive"))
    )
    (net (code "61") (name "/P6D_P") (class "Default")
      (node (ref "J1") (pin "31") (pinfunction "31_31") (pintype "passive"))
      (node (ref "U1") (pin "62") (pinfunction "P6MDIDP_62") (pintype "passive"))
    )
    (net (code "62") (name "/P7A_N") (class "Default")
      (node (ref "J1") (pin "34") (pinfunction "34_34") (pintype "passive"))
      (node (ref "U1") (pin "66") (pinfunction "P7MDIAN_66") (pintype "passive"))
    )
    (net (code "63") (name "/P7A_P") (class "Default")
      (node (ref "J1") (pin "33") (pinfunction "33_33") (pintype "passive"))
      (node (ref "U1") (pin "65") (pinfunction "P7MDIAP_65") (pintype "passive"))
    )
    (net (code "64") (name "/P7B_N") (class "Default")
      (node (ref "J1") (pin "36") (pinfunction "36_36") (pintype "passive"))
      (node (ref "U1") (pin "68") (pinfunction "P7MDIBN_68") (pintype "passive"))
    )
    (net (code "65") (name "/P7B_P") (class "Default")
      (node (ref "J1") (pin "35") (pinfunction "35_35") (pintype "passive"))
      (node (ref "U1") (pin "67") (pinfunction "P7MDIBP_67") (pintype "passive"))
    )
    (net (code "66") (name "/P7C_N") (class "Default")
      (node (ref "J1") (pin "38") (pinfunction "38_38") (pintype "passive"))
      (node (ref "U1") (pin "71") (pinfunction "P7MDICN_71") (pintype "passive"))
    )
    (net (code "67") (name "/P7C_P") (class "Default")
      (node (ref "J1") (pin "37") (pinfunction "37_37") (pintype "passive"))
      (node (ref "U1") (pin "70") (pinfunction "P7MDICP_70") (pintype "passive"))
    )
    (net (code "68") (name "/P7D_N") (class "Default")
      (node (ref "J1") (pin "40") (pinfunction "40_40") (pintype "passive"))
      (node (ref "U1") (pin "73") (pinfunction "P7MDIDN_73") (pintype "passive"))
    )
    (net (code "69") (name "/P7D_P") (class "Default")
      (node (ref "J1") (pin "39") (pinfunction "39_39") (pintype "passive"))
      (node (ref "U1") (pin "72") (pinfunction "P7MDIDP_72") (pintype "passive"))
    )
    (net (code "70") (name "/SMI_SEL") (class "Default")
      (node (ref "R8") (pin "2") (pinfunction "2_2") (pintype "passive"))
      (node (ref "U1") (pin "135") (pinfunction "LED_CK/P0LED0/SLED_P4B/SMI_SEL_135") (pintype "passive"))
    )
    (net (code "71") (name "/nRST") (class "Default")
      (node (ref "C7") (pin "2") (pinfunction "2_2") (pintype "passive"))
      (node (ref "R12") (pin "1") (pinfunction "1_1") (pintype "passive"))
      (node (ref "U1") (pin "141") (pinfunction "nRESET_141") (pintype "passive"))
    )
    (net (code "72") (name "1V") (class "Default")
      (node (ref "C2") (pin "2") (pinfunction "2_2") (pintype "passive"))
      (node (ref "C3") (pin "2") (pinfunction "2_2") (pintype "passive"))
      (node (ref "C4") (pin "2") (pinfunction "2_2") (pintype "passive"))
      (node (ref "FB3") (pin "1") (pinfunction "1_1") (pintype "passive"))
      (node (ref "FB4") (pin "1") (pinfunction "1_1") (pintype "passive"))
      (node (ref "FB6") (pin "1") (pinfunction "1_1") (pintype "passive"))
      (node (ref "FB7") (pin "1") (pinfunction "1_1") (pintype "passive"))
      (node (ref "L1") (pin "2") (pinfunction "2_2") (pintype "passive"))
      (node (ref "R1") (pin "2") (pinfunction "2_2") (pintype "passive"))
    )
    (net (code "73") (name "3V3") (class "Default")
      (node (ref "C30") (pin "2") (pinfunction "2_2") (pintype "passive"))
      (node (ref "FB1") (pin "1") (pinfunction "1_1") (pintype "passive"))
      (node (ref "FB2") (pin "1") (pinfunction "1_1") (pintype "passive"))
      (node (ref "R12") (pin "2") (pinfunction "2_2") (pintype "passive"))
      (node (ref "R13") (pin "2") (pinfunction "2_2") (pintype "passive"))
      (node (ref "R14") (pin "1") (pinfunction "1_1") (pintype "passive"))
      (node (ref "R15") (pin "1") (pinfunction "1_1") (pintype "passive"))
      (node (ref "R18") (pin "2") (pinfunction "2_2") (pintype "passive"))
      (node (ref "R4") (pin "1") (pinfunction "1_1") (pintype "passive"))
      (node (ref "R8") (pin "1") (pinfunction "1_1") (pintype "passive"))
      (node (ref "Rp6") (pin "1") (pinfunction "1_1") (pintype "passive"))
      (node (ref "Rp6") (pin "3") (pinfunction "3_3") (pintype "passive"))
      (node (ref "Rp8") (pin "2") (pinfunction "2_2") (pintype "passive"))
      (node (ref "Rp8") (pin "3") (pinfunction "3_3") (pintype "passive"))
      (node (ref "Rp8") (pin "4") (pinfunction "4_4") (pintype "passive"))
      (node (ref "U3") (pin "8") (pinfunction "VCC_8") (pintype "power_in"))
      (node (ref "VR1") (pin "2") (pinfunction "Vout_2") (pintype "passive"))
    )
    (net (code "74") (name "AVDDH") (class "Default")
      (node (ref "C15") (pin "2") (pinfunction "2_2") (pintype "passive"))
      (node (ref "C16") (pin "2") (pinfunction "2_2") (pintype "passive"))
      (node (ref "C17") (pin "2") (pinfunction "2_2") (pintype "passive"))
      (node (ref "C18") (pin "2") (pinfunction "2_2") (pintype "passive"))
      (node (ref "C19") (pin "2") (pinfunction "2_2") (pintype "passive"))
      (node (ref "C20") (pin "2") (pinfunction "2_2") (pintype "passive"))
      (node (ref "C21") (pin "2") (pinfunction "2_2") (pintype "passive"))
      (node (ref "C22") (pin "2") (pinfunction "2_2") (pintype "passive"))
      (node (ref "C23") (pin "2") (pinfunction "2_2") (pintype "passive"))
      (node (ref "C24") (pin "2") (pinfunction "2_2") (pintype "passive"))
      (node (ref "C25") (pin "2") (pinfunction "2_2") (pintype "passive"))
      (node (ref "C26") (pin "2") (pinfunction "2_2") (pintype "passive"))
      (node (ref "C27") (pin "2") (pinfunction "2_2") (pintype "passive"))
      (node (ref "C28") (pin "2") (pinfunction "2_2") (pintype "passive"))
      (node (ref "FB2") (pin "2") (pinfunction "2_2") (pintype "passive"))
      (node (ref "U1") (pin "1") (pinfunction "AVDDH_1") (pintype "passive"))
      (node (ref "U1") (pin "11") (pinfunction "AVDDH_11") (pintype "passive"))
      (node (ref "U1") (pin "137") (pinfunction "AVDDH_137") (pintype "passive"))
      (node (ref "U1") (pin "144") (pinfunction "AVDDH_144") (pintype "passive"))
      (node (ref "U1") (pin "154") (pinfunction "AVDDH_154") (pintype "passive"))
      (node (ref "U1") (pin "167") (pinfunction "AVDDH_167") (pintype "passive"))
      (node (ref "U1") (pin "20") (pinfunction "AVDDH_20") (pintype "passive"))
      (node (ref "U1") (pin "32") (pinfunction "AVDDH_32") (pintype "passive"))
      (node (ref "U1") (pin "42") (pinfunction "AVDDH_42") (pintype "passive"))
      (node (ref "U1") (pin "54") (pinfunction "AVDDH_54") (pintype "passive"))
      (node (ref "U1") (pin "64") (pinfunction "AVDDH_64") (pintype "passive"))
      (node (ref "U1") (pin "74") (pinfunction "AVDDH_74") (pintype "passive"))
    )
    (net (code "75") (name "AVDDL") (class "Default")
      (node (ref "C31") (pin "2") (pinfunction "2_2") (pintype "passive"))
      (node (ref "C32") (pin "2") (pinfunction "2_2") (pintype "passive"))
      (node (ref "C33") (pin "2") (pinfunction "2_2") (pintype "passive"))
      (node (ref "C34") (pin "2") (pinfunction "2_2") (pintype "passive"))
      (node (ref "C35") (pin "2") (pinfunction "2_2") (pintype "passive"))
      (node (ref "C36") (pin "2") (pinfunction "2_2") (pintype "passive"))
      (node (ref "C37") (pin "2") (pinfunction "2_2") (pintype "passive"))
      (node (ref "C38") (pin "2") (pinfunction "2_2") (pintype "passive"))
      (node (ref "C39") (pin "2") (pinfunction "2_2") (pintype "passive"))
      (node (ref "C40") (pin "2") (pinfunction "2_2") (pintype "passive"))
      (node (ref "FB3") (pin "2") (pinfunction "2_2") (pintype "passive"))
      (node (ref "U1") (pin "149") (pinfunction "AVDDL_149") (pintype "passive"))
      (node (ref "U1") (pin "159") (pinfunction "AVDDL_159") (pintype "passive"))
      (node (ref "U1") (pin "17") (pinfunction "AVDDL_17") (pintype "passive"))
      (node (ref "U1") (pin "172") (pinfunction "AVDDL_172") (pintype "passive"))
      (node (ref "U1") (pin "37") (pinfunction "AVDDL_37") (pintype "passive"))
      (node (ref "U1") (pin "47") (pinfunction "AVDDL_47") (pintype "passive"))
      (node (ref "U1") (pin "59") (pinfunction "AVDDL_59") (pintype "passive"))
      (node (ref "U1") (pin "6") (pinfunction "AVDDL_6") (pintype "passive"))
      (node (ref "U1") (pin "69") (pinfunction "AVDDL_69") (pintype "passive"))
    )
    (net (code "76") (name "DVDDIO") (class "Default")
      (node (ref "C10") (pin "2") (pinfunction "2_2") (pintype "passive"))
      (node (ref "C11") (pin "2") (pinfunction "2_2") (pintype "passive"))
      (node (ref "C12") (pin "2") (pinfunction "2_2") (pintype "passive"))
      (node (ref "C13") (pin "2") (pinfunction "2_2") (pintype "passive"))
      (node (ref "C14") (pin "2") (pinfunction "2_2") (pintype "passive"))
      (node (ref "C8") (pin "2") (pinfunction "2_2") (pintype "passive"))
      (node (ref "C9") (pin "2") (pinfunction "2_2") (pintype "passive"))
      (node (ref "FB1") (pin "2") (pinfunction "2_2") (pintype "passive"))
      (node (ref "U1") (pin "104") (pinfunction "DVDDIO_1_104") (pintype "passive"))
      (node (ref "U1") (pin "105") (pinfunction "DVDDIO_0_105") (pintype "passive"))
      (node (ref "U1") (pin "132") (pinfunction "DVDDIO_0_132") (pintype "passive"))
      (node (ref "U1") (pin "140") (pinfunction "DVDDIO_140") (pintype "passive"))
      (node (ref "U1") (pin "21") (pinfunction "DVDDIO_21") (pintype "passive"))
      (node (ref "U1") (pin "88") (pinfunction "DVDDIO_1_88") (pintype "passive"))
    )
    (net (code "77") (name "DVDDL") (class "Default")
      (node (ref "C41") (pin "2") (pinfunction "2_2") (pintype "passive"))
      (node (ref "C42") (pin "2") (pinfunction "2_2") (pintype "passive"))
      (node (ref "C43") (pin "2") (pinfunction "2_2") (pintype "passive"))
      (node (ref "C44") (pin "2") (pinfunction "2_2") (pintype "passive"))
      (node (ref "C45") (pin "2") (pinfunction "2_2") (pintype "passive"))
      (node (ref "C46") (pin "2") (pinfunction "2_2") (pintype "passive"))
      (node (ref "C47") (pin "2") (pinfunction "2_2") (pintype "passive"))
      (node (ref "C48") (pin "2") (pinfunction "2_2") (pintype "passive"))
      (node (ref "C49") (pin "2") (pinfunction "2_2") (pintype "passive"))
      (node (ref "C50") (pin "2") (pinfunction "2_2") (pintype "passive"))
      (node (ref "FB4") (pin "2") (pinfunction "2_2") (pintype "passive"))
      (node (ref "U1") (pin "103") (pinfunction "DVDDL_103") (pintype "passive"))
      (node (ref "U1") (pin "106") (pinfunction "DVDDL_106") (pintype "passive"))
      (node (ref "U1") (pin "133") (pinfunction "DVDDL_133") (pintype "passive"))
      (node (ref "U1") (pin "136") (pinfunction "DVDDL_136") (pintype "passive"))
      (node (ref "U1") (pin "22") (pinfunction "DVDDL_22") (pintype "passive"))
      (node (ref "U1") (pin "26") (pinfunction "DVDDL_26") (pintype "passive"))
      (node (ref "U1") (pin "29") (pinfunction "DVDDL_29") (pintype "passive"))
      (node (ref "U1") (pin "30") (pinfunction "DVDDL_30") (pintype "passive"))
    )
    (net (code "78") (name "GND") (class "Default")
      (node (ref "C1") (pin "1") (pinfunction "1_1") (pintype "passive"))
      (node (ref "C10") (pin "1") (pinfunction "1_1") (pintype "passive"))
      (node (ref "C11") (pin "1") (pinfunction "1_1") (pintype "passive"))
      (node (ref "C12") (pin "1") (pinfunction "1_1") (pintype "passive"))
      (node (ref "C13") (pin "1") (pinfunction "1_1") (pintype "passive"))
      (node (ref "C14") (pin "1") (pinfunction "1_1") (pintype "passive"))
      (node (ref "C15") (pin "1") (pinfunction "1_1") (pintype "passive"))
      (node (ref "C16") (pin "1") (pinfunction "1_1") (pintype "passive"))
      (node (ref "C17") (pin "1") (pinfunction "1_1") (pintype "passive"))
      (node (ref "C18") (pin "1") (pinfunction "1_1") (pintype "passive"))
      (node (ref "C19") (pin "1") (pinfunction "1_1") (pintype "passive"))
      (node (ref "C2") (pin "1") (pinfunction "1_1") (pintype "passive"))
      (node (ref "C20") (pin "1") (pinfunction "1_1") (pintype "passive"))
      (node (ref "C21") (pin "1") (pinfunction "1_1") (pintype "passive"))
      (node (ref "C22") (pin "1") (pinfunction "1_1") (pintype "passive"))
      (node (ref "C23") (pin "1") (pinfunction "1_1") (pintype "passive"))
      (node (ref "C24") (pin "1") (pinfunction "1_1") (pintype "passive"))
      (node (ref "C25") (pin "1") (pinfunction "1_1") (pintype "passive"))
      (node (ref "C26") (pin "1") (pinfunction "1_1") (pintype "passive"))
      (node (ref "C27") (pin "1") (pinfunction "1_1") (pintype "passive"))
      (node (ref "C28") (pin "1") (pinfunction "1_1") (pintype "passive"))
      (node (ref "C29") (pin "1") (pinfunction "1_1") (pintype "passive"))
      (node (ref "C3") (pin "1") (pinfunction "1_1") (pintype "passive"))
      (node (ref "C30") (pin "1") (pinfunction "1_1") (pintype "passive"))
      (node (ref "C31") (pin "1") (pinfunction "1_1") (pintype "passive"))
      (node (ref "C32") (pin "1") (pinfunction "1_1") (pintype "passive"))
      (node (ref "C33") (pin "1") (pinfunction "1_1") (pintype "passive"))
      (node (ref "C34") (pin "1") (pinfunction "1_1") (pintype "passive"))
      (node (ref "C35") (pin "1") (pinfunction "1_1") (pintype "passive"))
      (node (ref "C36") (pin "1") (pinfunction "1_1") (pintype "passive"))
      (node (ref "C37") (pin "1") (pinfunction "1_1") (pintype "passive"))
      (node (ref "C38") (pin "1") (pinfunction "1_1") (pintype "passive"))
      (node (ref "C39") (pin "1") (pinfunction "1_1") (pintype "passive"))
      (node (ref "C4") (pin "1") (pinfunction "1_1") (pintype "passive"))
      (node (ref "C40") (pin "1") (pinfunction "1_1") (pintype "passive"))
      (node (ref "C41") (pin "1") (pinfunction "1_1") (pintype "passive"))
      (node (ref "C42") (pin "1") (pinfunction "1_1") (pintype "passive"))
      (node (ref "C43") (pin "1") (pinfunction "1_1") (pintype "passive"))
      (node (ref "C44") (pin "1") (pinfunction "1_1") (pintype "passive"))
      (node (ref "C45") (pin "1") (pinfunction "1_1") (pintype "passive"))
      (node (ref "C46") (pin "1") (pinfunction "1_1") (pintype "passive"))
      (node (ref "C47") (pin "1") (pinfunction "1_1") (pintype "passive"))
      (node (ref "C48") (pin "1") (pinfunction "1_1") (pintype "passive"))
      (node (ref "C49") (pin "1") (pinfunction "1_1") (pintype "passive"))
      (node (ref "C5") (pin "1") (pinfunction "1_1") (pintype "passive"))
      (node (ref "C50") (pin "1") (pinfunction "1_1") (pintype "passive"))
      (node (ref "C53") (pin "1") (pinfunction "1_1") (pintype "passive"))
      (node (ref "C54") (pin "1") (pinfunction "1_1") (pintype "passive"))
      (node (ref "C55") (pin "1") (pinfunction "1_1") (pintype "passive"))
      (node (ref "C56") (pin "1") (pinfunction "1_1") (pintype "passive"))
      (node (ref "C6") (pin "1") (pinfunction "1_1") (pintype "passive"))
      (node (ref "C7") (pin "1") (pinfunction "1_1") (pintype "passive"))
      (node (ref "C8") (pin "1") (pinfunction "1_1") (pintype "passive"))
      (node (ref "C9") (pin "1") (pinfunction "1_1") (pintype "passive"))
      (node (ref "J1") (pin "17") (pinfunction "17_17") (pintype "passive"))
      (node (ref "J1") (pin "19") (pinfunction "19_19") (pintype "passive"))
      (node (ref "J1") (pin "21") (pinfunction "21_21") (pintype "passive"))
      (node (ref "J1") (pin "23") (pinfunction "23_23") (pintype "passive"))
      (node (ref "J2") (pin "17") (pinfunction "17_17") (pintype "passive"))
      (node (ref "J2") (pin "19") (pinfunction "19_19") (pintype "passive"))
      (node (ref "J2") (pin "21") (pinfunction "21_21") (pintype "passive"))
      (node (ref "J2") (pin "23") (pinfunction "23_23") (pintype "passive"))
      (node (ref "R11") (pin "1") (pinfunction "1_1") (pintype "passive"))
      (node (ref "R16") (pin "1") (pinfunction "1_1") (pintype "passive"))
      (node (ref "R17") (pin "1") (pinfunction "1_1") (pintype "passive"))
      (node (ref "R2") (pin "1") (pinfunction "1_1") (pintype "passive"))
      (node (ref "R3") (pin "1") (pinfunction "1_1") (pintype "passive"))
      (node (ref "Rp1") (pin "5") (pinfunction "5_5") (pintype "passive"))
      (node (ref "Rp1") (pin "6") (pinfunction "6_6") (pintype "passive"))
      (node (ref "Rp1") (pin "7") (pinfunction "7_7") (pintype "passive"))
      (node (ref "Rp1") (pin "8") (pinfunction "8_8") (pintype "passive"))
      (node (ref "Rp10") (pin "2") (pinfunction "2_2") (pintype "passive"))
      (node (ref "Rp10") (pin "3") (pinfunction "3_3") (pintype "passive"))
      (node (ref "Rp10") (pin "4") (pinfunction "4_4") (pintype "passive"))
      (node (ref "Rp2") (pin "5") (pinfunction "5_5") (pintype "passive"))
      (node (ref "Rp2") (pin "6") (pinfunction "6_6") (pintype "passive"))
      (node (ref "Rp2") (pin "7") (pinfunction "7_7") (pintype "passive"))
      (node (ref "Rp2") (pin "8") (pinfunction "8_8") (pintype "passive"))
      (node (ref "Rp3") (pin "5") (pinfunction "5_5") (pintype "passive"))
      (node (ref "Rp3") (pin "6") (pinfunction "6_6") (pintype "passive"))
      (node (ref "Rp3") (pin "7") (pinfunction "7_7") (pintype "passive"))
      (node (ref "Rp3") (pin "8") (pinfunction "8_8") (pintype "passive"))
      (node (ref "Rp4") (pin "5") (pinfunction "5_5") (pintype "passive"))
      (node (ref "Rp4") (pin "6") (pinfunction "6_6") (pintype "passive"))
      (node (ref "Rp4") (pin "7") (pinfunction "7_7") (pintype "passive"))
      (node (ref "Rp4") (pin "8") (pinfunction "8_8") (pintype "passive"))
      (node (ref "Rp5") (pin "1") (pinfunction "1_1") (pintype "passive"))
      (node (ref "Rp5") (pin "2") (pinfunction "2_2") (pintype "passive"))
      (node (ref "Rp5") (pin "3") (pinfunction "3_3") (pintype "passive"))
      (node (ref "Rp5") (pin "4") (pinfunction "4_4") (pintype "passive"))
      (node (ref "Rp6") (pin "2") (pinfunction "2_2") (pintype "passive"))
      (node (ref "Rp6") (pin "4") (pinfunction "4_4") (pintype "passive"))
      (node (ref "Rp7") (pin "1") (pinfunction "1_1") (pintype "passive"))
      (node (ref "Rp7") (pin "2") (pinfunction "2_2") (pintype "passive"))
      (node (ref "Rp7") (pin "3") (pinfunction "3_3") (pintype "passive"))
      (node (ref "Rp7") (pin "4") (pinfunction "4_4") (pintype "passive"))
      (node (ref "Rp8") (pin "1") (pinfunction "1_1") (pintype "passive"))
      (node (ref "Rp9") (pin "1") (pinfunction "1_1") (pintype "passive"))
      (node (ref "Rp9") (pin "2") (pinfunction "2_2") (pintype "passive"))
      (node (ref "Rp9") (pin "3") (pinfunction "3_3") (pintype "passive"))
      (node (ref "Rp9") (pin "4") (pinfunction "4_4") (pintype "passive"))
      (node (ref "U1") (pin "12") (pinfunction "GND_12") (pintype "passive"))
      (node (ref "U1") (pin "15") (pinfunction "AGND_15") (pintype "passive"))
      (node (ref "U1") (pin "166") (pinfunction "PLLGND0_166") (pintype "passive"))
      (node (ref "U1") (pin "177") (pinfunction "GND_177") (pintype "passive"))
      (node (ref "U1") (pin "23") (pinfunction "GND_23") (pintype "passive"))
      (node (ref "U1") (pin "28") (pinfunction "GND_28") (pintype "passive"))
      (node (ref "U1") (pin "31") (pinfunction "GND_31") (pintype "passive"))
      (node (ref "U1") (pin "53") (pinfunction "PLLGND1_53") (pintype "passive"))
      (node (ref "U2") (pin "2") (pinfunction "GND_2") (pintype "power_in"))
      (node (ref "U3") (pin "1") (pinfunction "E0_1") (pintype "input"))
      (node (ref "U3") (pin "2") (pinfunction "E1_2") (pintype "input"))
      (node (ref "U3") (pin "3") (pinfunction "E2_3") (pintype "input"))
      (node (ref "U3") (pin "4") (pinfunction "GND_4") (pintype "power_in"))
      (node (ref "VR1") (pin "1") (pinfunction "GND_1") (pintype "passive"))
    )
    (net (code "79") (name "Net-(R16-Pad2)") (class "Default")
      (node (ref "R16") (pin "2") (pinfunction "2_2") (pintype "passive"))
      (node (ref "U1") (pin "13") (pinfunction "RESERVED_13") (pintype "passive"))
    )
    (net (code "80") (name "Net-(U1-G0_COL{slash}M0M_COL{slash}M0P_COL{slash}P4LED0{slash}SLED_P6B)") (class "Default")
      (node (ref "Rp1") (pin "2") (pinfunction "2_2") (pintype "passive"))
      (node (ref "U1") (pin "108") (pinfunction "G0_COL/M0M_COL/M0P_COL/P4LED0/SLED_P6B_108") (pintype "passive"))
    )
    (net (code "81") (name "Net-(U1-G0_CRS{slash}M0M_CRS{slash}M0P_CRS{slash}P4LED2{slash}SLED_P7B{slash}GPIO3)") (class "Default")
      (node (ref "Rp1") (pin "1") (pinfunction "1_1") (pintype "passive"))
      (node (ref "U1") (pin "107") (pinfunction "G0_CRS/M0M_CRS/M0P_CRS/P4LED2/SLED_P7B/GPIO3_107") (pintype "passive"))
    )
    (net (code "82") (name "Net-(U1-G0_RXC{slash}RG0_RXCLK{slash}M0M_RXCLK{slash}M0P_TXCLK)") (class "Default")
      (node (ref "Rp3") (pin "4") (pinfunction "4_4") (pintype "passive"))
      (node (ref "U1") (pin "118") (pinfunction "G0_RXC/RG0_RXCLK/M0M_RXCLK/M0P_TXCLK_118") (pintype "passive"))
    )
    (net (code "83") (name "Net-(U1-G0_RXD0{slash}RG0_RXD0{slash}M0M_RXD0{slash}M0P_TXD0)") (class "Default")
      (node (ref "Rp3") (pin "2") (pinfunction "2_2") (pintype "passive"))
      (node (ref "U1") (pin "116") (pinfunction "G0_RXD0/RG0_RXD0/M0M_RXD0/M0P_TXD0_116") (pintype "passive"))
    )
    (net (code "84") (name "Net-(U1-G0_RXD1{slash}RG0_RXD1{slash}M0M_RXD1{slash}M0P_TXD1)") (class "Default")
      (node (ref "Rp3") (pin "1") (pinfunction "1_1") (pintype "passive"))
      (node (ref "U1") (pin "115") (pinfunction "G0_RXD1/RG0_RXD1/M0M_RXD1/M0P_TXD1_115") (pintype "passive"))
    )
    (net (code "85") (name "Net-(U1-G0_RXD2{slash}RG0_RXD2{slash}M0M_RXD2{slash}M0P_TXD2)") (class "Default")
      (node (ref "Rp2") (pin "4") (pinfunction "4_4") (pintype "passive"))
      (node (ref "U1") (pin "114") (pinfunction "G0_RXD2/RG0_RXD2/M0M_RXD2/M0P_TXD2_114") (pintype "passive"))
    )
    (net (code "86") (name "Net-(U1-G0_RXD3{slash}RG0_RXD3{slash}M0M_RXD3{slash}M0P_TXD3)") (class "Default")
      (node (ref "Rp2") (pin "3") (pinfunction "3_3") (pintype "passive"))
      (node (ref "U1") (pin "113") (pinfunction "G0_RXD3/RG0_RXD3/M0M_RXD3/M0P_TXD3_113") (pintype "passive"))
    )
    (net (code "87") (name "Net-(U1-G0_RXD4{slash}P3LED0{slash}SLED_P2B)") (class "Default")
      (node (ref "Rp2") (pin "2") (pinfunction "2_2") (pintype "passive"))
      (node (ref "U1") (pin "112") (pinfunction "G0_RXD4/P3LED0/SLED_P2B_112") (pintype "passive"))
    )
    (net (code "88") (name "Net-(U1-G0_RXD5{slash}P3LED2{slash}SLED_P3B)") (class "Default")
      (node (ref "Rp2") (pin "1") (pinfunction "1_1") (pintype "passive"))
      (node (ref "U1") (pin "111") (pinfunction "G0_RXD5/P3LED2/SLED_P3B_111") (pintype "passive"))
    )
    (net (code "89") (name "Net-(U1-G0_RXD6{slash}P3LED1{slash}SLED_G1A)") (class "Default")
      (node (ref "Rp1") (pin "4") (pinfunction "4_4") (pintype "passive"))
      (node (ref "U1") (pin "110") (pinfunction "G0_RXD6/P3LED1/SLED_G1A_110") (pintype "passive"))
    )
    (net (code "90") (name "Net-(U1-G0_RXD7{slash}P4LED1{slash}SLED_P5B)") (class "Default")
      (node (ref "Rp1") (pin "3") (pinfunction "3_3") (pintype "passive"))
      (node (ref "U1") (pin "109") (pinfunction "G0_RXD7/P4LED1/SLED_P5B_109") (pintype "passive"))
    )
    (net (code "91") (name "Net-(U1-G0_RXDV{slash}RG0_RXCTL{slash}M0M_RXDV{slash}M0P_TXEN{slash}GPIO6)") (class "Default")
      (node (ref "Rp3") (pin "3") (pinfunction "3_3") (pintype "passive"))
      (node (ref "U1") (pin "117") (pinfunction "G0_RXDV/RG0_RXCTL/M0M_RXDV/M0P_TXEN/GPIO6_117") (pintype "passive"))
    )
    (net (code "92") (name "Net-(U1-G0_RXER{slash}P2LED2{slash}GPIO7{slash}SLED_P1B)") (class "Default")
      (node (ref "Rp4") (pin "1") (pinfunction "1_1") (pintype "passive"))
      (node (ref "U1") (pin "119") (pinfunction "G0_RXER/P2LED2/GPIO7/SLED_P1B_119") (pintype "passive"))
    )
    (net (code "93") (name "Net-(U1-G0_TXCLK{slash}P2LED1{slash}SLED_G1B)") (class "Default")
      (node (ref "Rp4") (pin "2") (pinfunction "2_2") (pintype "passive"))
      (node (ref "U1") (pin "121") (pinfunction "G0_TXCLK/P2LED1/SLED_G1B_121") (pintype "passive"))
    )
    (net (code "94") (name "Net-(U1-G0_TXD3{slash}RG0_TXD3{slash}M0M_TXD3{slash}M0P_RXD3{slash}RESERVED{slash}GPIO4)") (class "Default")
      (node (ref "Rp8") (pin "5") (pinfunction "5_5") (pintype "passive"))
      (node (ref "U1") (pin "127") (pinfunction "G0_TXD3/RG0_TXD3/M0M_TXD3/M0P_RXD3/RESERVED/GPIO4_127") (pintype "passive"))
    )
    (net (code "95") (name "Net-(U1-G0_TXD4{slash}P1LED2{slash}SLED_P3_7A{slash}RESERVED)") (class "Default")
      (node (ref "Rp8") (pin "6") (pinfunction "6_6") (pintype "passive"))
      (node (ref "U1") (pin "128") (pinfunction "G0_TXD4/P1LED2/SLED_P3_7A/RESERVED_128") (pintype "passive"))
    )
    (net (code "96") (name "Net-(U1-G0_TXD5{slash}P1LED0{slash}SLED_P2_6A{slash}RESERVED)") (class "Default")
      (node (ref "Rp8") (pin "7") (pinfunction "7_7") (pintype "passive"))
      (node (ref "U1") (pin "129") (pinfunction "G0_TXD5/P1LED0/SLED_P2_6A/RESERVED_129") (pintype "passive"))
    )
    (net (code "97") (name "Net-(U1-G0_TXEN{slash}RG0_TXCTL{slash}M0M_TXEN{slash}M0P_RXDV{slash}RESERVED)") (class "Default")
      (node (ref "Rp6") (pin "6") (pinfunction "6_6") (pintype "passive"))
      (node (ref "U1") (pin "123") (pinfunction "G0_TXEN/RG0_TXCTL/M0M_TXEN/M0P_RXDV/RESERVED_123") (pintype "passive"))
    )
    (net (code "98") (name "Net-(U1-G0_TXER{slash}P2LED0{slash}EEPROM_MOD{slash}SLED_P0B)") (class "Default")
      (node (ref "Rp6") (pin "5") (pinfunction "5_5") (pintype "passive"))
      (node (ref "U1") (pin "120") (pinfunction "G0_TXER/P2LED0/EEPROM_MOD/SLED_P0B_120") (pintype "passive"))
    )
    (net (code "99") (name "Net-(U1-G1_COL{slash}M1M_COL{slash}M1P_COL)") (class "Default")
      (node (ref "Rp10") (pin "6") (pinfunction "6_6") (pintype "passive"))
      (node (ref "U1") (pin "78") (pinfunction "G1_COL/M1M_COL/M1P_COL_78") (pintype "passive"))
    )
    (net (code "100") (name "Net-(U1-G1_CRS{slash}M1M_CRS{slash}M1P_CRS)") (class "Default")
      (node (ref "Rp10") (pin "5") (pinfunction "5_5") (pintype "passive"))
      (node (ref "U1") (pin "77") (pinfunction "G1_CRS/M1M_CRS/M1P_CRS_77") (pintype "passive"))
    )
    (net (code "101") (name "Net-(U1-G1_GTXC{slash}RG1_TXCLK{slash}M1M_TXCLK{slash}M1P_RXCLK)") (class "Default")
      (node (ref "Rp10") (pin "7") (pinfunction "7_7") (pintype "passive"))
      (node (ref "U1") (pin "89") (pinfunction "G1_GTXC/RG1_TXCLK/M1M_TXCLK/M1P_RXCLK_89") (pintype "passive"))
    )
    (net (code "102") (name "Net-(U1-G1_RXC{slash}RG1_RXCLK{slash}M1M_RXCLK{slash}M1P_TXCLK)") (class "Default")
      (node (ref "Rp9") (pin "7") (pinfunction "7_7") (pintype "passive"))
      (node (ref "U1") (pin "93") (pinfunction "G1_RXC/RG1_RXCLK/M1M_RXCLK/M1P_TXCLK_93") (pintype "passive"))
    )
    (net (code "103") (name "Net-(U1-G1_RXD0{slash}RG1_RXD0{slash}M1M_RXD0{slash}M1P_TXD0)") (class "Default")
      (node (ref "Rp7") (pin "5") (pinfunction "5_5") (pintype "passive"))
      (node (ref "U1") (pin "95") (pinfunction "G1_RXD0/RG1_RXD0/M1M_RXD0/M1P_TXD0_95") (pintype "passive"))
    )
    (net (code "104") (name "Net-(U1-G1_RXD1{slash}RG1_RXD1{slash}M1M_RXD1{slash}M1P_TXD1)") (class "Default")
      (node (ref "Rp7") (pin "6") (pinfunction "6_6") (pintype "passive"))
      (node (ref "U1") (pin "96") (pinfunction "G1_RXD1/RG1_RXD1/M1M_RXD1/M1P_TXD1_96") (pintype "passive"))
    )
    (net (code "105") (name "Net-(U1-G1_RXD2{slash}RG1_RXD2{slash}M1M_RXD2{slash}M1P_TXD2)") (class "Default")
      (node (ref "Rp7") (pin "7") (pinfunction "7_7") (pintype "passive"))
      (node (ref "U1") (pin "97") (pinfunction "G1_RXD2/RG1_RXD2/M1M_RXD2/M1P_TXD2_97") (pintype "passive"))
    )
    (net (code "106") (name "Net-(U1-G1_RXD3{slash}RG1_RXD3{slash}M1M_RXD3{slash}M1P_TXD3)") (class "Default")
      (node (ref "Rp7") (pin "8") (pinfunction "8_8") (pintype "passive"))
      (node (ref "U1") (pin "98") (pinfunction "G1_RXD3/RG1_RXD3/M1M_RXD3/M1P_TXD3_98") (pintype "passive"))
    )
    (net (code "107") (name "Net-(U1-G1_RXD4{slash}P6LED1)") (class "Default")
      (node (ref "Rp5") (pin "5") (pinfunction "5_5") (pintype "passive"))
      (node (ref "U1") (pin "99") (pinfunction "G1_RXD4/P6LED1_99") (pintype "passive"))
    )
    (net (code "108") (name "Net-(U1-G1_RXD5{slash}P5LED2{slash}GPIO0)") (class "Default")
      (node (ref "Rp5") (pin "6") (pinfunction "6_6") (pintype "passive"))
      (node (ref "U1") (pin "100") (pinfunction "G1_RXD5/P5LED2/GPIO0_100") (pintype "passive"))
    )
    (net (code "109") (name "Net-(U1-G1_RXD6{slash}P5LED0)") (class "Default")
      (node (ref "Rp5") (pin "7") (pinfunction "7_7") (pintype "passive"))
      (node (ref "U1") (pin "101") (pinfunction "G1_RXD6/P5LED0_101") (pintype "passive"))
    )
    (net (code "110") (name "Net-(U1-G1_RXD7{slash}P5LED1)") (class "Default")
      (node (ref "Rp5") (pin "8") (pinfunction "8_8") (pintype "passive"))
      (node (ref "U1") (pin "102") (pinfunction "G1_RXD7/P5LED1_102") (pintype "passive"))
    )
    (net (code "111") (name "Net-(U1-G1_RXDV{slash}RG1_RXCTL{slash}M1M_RXDV{slash}M1P_TXEN)") (class "Default")
      (node (ref "Rp9") (pin "8") (pinfunction "8_8") (pintype "passive"))
      (node (ref "U1") (pin "94") (pinfunction "G1_RXDV/RG1_RXCTL/M1M_RXDV/M1P_TXEN_94") (pintype "passive"))
    )
    (net (code "112") (name "Net-(U1-G1_RXER{slash}M1M_RXER{slash}M1P_TXER)") (class "Default")
      (node (ref "Rp9") (pin "6") (pinfunction "6_6") (pintype "passive"))
      (node (ref "U1") (pin "92") (pinfunction "G1_RXER/M1M_RXER/M1P_TXER_92") (pintype "passive"))
    )
    (net (code "113") (name "Net-(U1-G1_TXCLK{slash}P6LED0{slash}GPIO1)") (class "Default")
      (node (ref "Rp9") (pin "5") (pinfunction "5_5") (pintype "passive"))
      (node (ref "U1") (pin "90") (pinfunction "G1_TXCLK/P6LED0/GPIO1_90") (pintype "passive"))
    )
    (net (code "114") (name "Net-(U1-G1_TXER{slash}M1M_TXER{slash}M1P_RXER{slash}RESERVED)") (class "Default")
      (node (ref "R11") (pin "2") (pinfunction "2_2") (pintype "passive"))
      (node (ref "U1") (pin "91") (pinfunction "G1_TXER/M1M_TXER/M1P_RXER/RESERVED_91") (pintype "passive"))
    )
    (net (code "115") (name "Net-(U1-MDIREF)") (class "Default")
      (node (ref "R17") (pin "2") (pinfunction "2_2") (pintype "passive"))
      (node (ref "U1") (pin "16") (pinfunction "MDIREF_16") (pintype "passive"))
    )
    (net (code "116") (name "Net-(U1-SCK{slash}MMD_MDC)") (class "Default")
      (node (ref "R13") (pin "1") (pinfunction "1_1") (pintype "passive"))
      (node (ref "U1") (pin "142") (pinfunction "SCK/MMD_MDC_142") (pintype "passive"))
      (node (ref "U3") (pin "6") (pinfunction "SCL_6") (pintype "input"))
    )
    (net (code "117") (name "Net-(U1-SDA{slash}MMD_MDIO)") (class "Default")
      (node (ref "R14") (pin "2") (pinfunction "2_2") (pintype "passive"))
      (node (ref "U1") (pin "143") (pinfunction "SDA/MMD_MDIO_143") (pintype "passive"))
      (node (ref "U3") (pin "5") (pinfunction "SDA_5") (pintype "bidirectional"))
    )
    (net (code "118") (name "Net-(U1-XTALI)") (class "Default")
      (node (ref "C6") (pin "2") (pinfunction "2_2") (pintype "passive"))
      (node (ref "U1") (pin "139") (pinfunction "XTALI_139") (pintype "passive"))
      (node (ref "Y1") (pin "1") (pinfunction "OSC1_1") (pintype "passive"))
    )
    (net (code "119") (name "Net-(U1-XTALO)") (class "Default")
      (node (ref "C5") (pin "2") (pinfunction "2_2") (pintype "passive"))
      (node (ref "U1") (pin "138") (pinfunction "XTALO_138") (pintype "passive"))
      (node (ref "Y1") (pin "3") (pinfunction "OSC2_3") (pintype "passive"))
    )
    (net (code "120") (name "Net-(U2-FB)") (class "Default")
      (node (ref "R1") (pin "1") (pinfunction "1_1") (pintype "passive"))
      (node (ref "R2") (pin "2") (pinfunction "2_2") (pintype "passive"))
      (node (ref "U2") (pin "5") (pinfunction "FB_5") (pintype "input"))
    )
    (net (code "121") (name "Net-(U2-SW)") (class "Default")
      (node (ref "L1") (pin "1") (pinfunction "1_1") (pintype "passive"))
      (node (ref "U2") (pin "3") (pinfunction "SW_3") (pintype "power_in"))
    )
    (net (code "122") (name "Net-(U3-MODE)") (class "Default")
      (node (ref "R15") (pin "2") (pinfunction "2_2") (pintype "passive"))
      (node (ref "U3") (pin "7") (pinfunction "MODE_7") (pintype "input"))
    )
    (net (code "123") (name "PLLVDDL0") (class "Default")
      (node (ref "C53") (pin "2") (pinfunction "2_2") (pintype "passive"))
      (node (ref "C54") (pin "2") (pinfunction "2_2") (pintype "passive"))
      (node (ref "FB6") (pin "2") (pinfunction "2_2") (pintype "passive"))
      (node (ref "U1") (pin "164") (pinfunction "PLLVDDL0_164") (pintype "passive"))
    )
    (net (code "124") (name "PLLVDDL1") (class "Default")
      (node (ref "C55") (pin "2") (pinfunction "2_2") (pintype "passive"))
      (node (ref "C56") (pin "2") (pinfunction "2_2") (pintype "passive"))
      (node (ref "FB7") (pin "2") (pinfunction "2_2") (pintype "passive"))
      (node (ref "U1") (pin "52") (pinfunction "PLLVDDL1_52") (pintype "passive"))
    )
    (net (code "125") (name "VCC") (class "Default")
      (node (ref "C1") (pin "2") (pinfunction "2_2") (pintype "passive"))
      (node (ref "C29") (pin "2") (pinfunction "2_2") (pintype "passive"))
      (node (ref "J1") (pin "18") (pinfunction "18_18") (pintype "passive"))
      (node (ref "J1") (pin "20") (pinfunction "20_20") (pintype "passive"))
      (node (ref "J1") (pin "22") (pinfunction "22_22") (pintype "passive"))
      (node (ref "J1") (pin "24") (pinfunction "24_24") (pintype "passive"))
      (node (ref "J2") (pin "18") (pinfunction "18_18") (pintype "passive"))
      (node (ref "J2") (pin "20") (pinfunction "20_20") (pintype "passive"))
      (node (ref "J2") (pin "22") (pinfunction "22_22") (pintype "passive"))
      (node (ref "J2") (pin "24") (pinfunction "24_24") (pintype "passive"))
      (node (ref "R18") (pin "1") (pinfunction "1_1") (pintype "passive"))
      (node (ref "U2") (pin "1") (pinfunction "EN_1") (pintype "input"))
      (node (ref "U2") (pin "4") (pinfunction "VIN_4") (pintype "power_in"))
      (node (ref "VR1") (pin "3") (pinfunction "Vin_3") (pintype "passive"))
    )
    (net (code "126") (name "unconnected-(Rp4-Pad3)") (class "Default")
      (node (ref "Rp4") (pin "3") (pinfunction "3_3") (pintype "passive"))
    )
    (net (code "127") (name "unconnected-(Rp4-Pad4)") (class "Default")
      (node (ref "Rp4") (pin "4") (pinfunction "4_4") (pintype "passive"))
    )
    (net (code "128") (name "unconnected-(Rp10-Pad1)") (class "Default")
      (node (ref "Rp10") (pin "1") (pinfunction "1_1") (pintype "passive"))
    )
    (net (code "129") (name "unconnected-(Rp10-Pad8)") (class "Default")
      (node (ref "Rp10") (pin "8") (pinfunction "8_8") (pintype "passive"))
    )
    (net (code "130") (name "unconnected-(TP1-Pad0)") (class "Default")
      (node (ref "TP1") (pin "0") (pinfunction "0_0") (pintype "passive"))
    )
    (net (code "131") (name "unconnected-(TP2-Pad0)") (class "Default")
      (node (ref "TP2") (pin "0") (pinfunction "0_0") (pintype "passive"))
    )
    (net (code "132") (name "unconnected-(TP3-Pad0)") (class "Default")
      (node (ref "TP3") (pin "0") (pinfunction "0_0") (pintype "passive"))
    )
    (net (code "133") (name "unconnected-(TP4-Pad0)") (class "Default")
      (node (ref "TP4") (pin "0") (pinfunction "0_0") (pintype "passive"))
    )
    (net (code "134") (name "unconnected-(TP5-Pad0)") (class "Default")
      (node (ref "TP5") (pin "0") (pinfunction "0_0") (pintype "passive"))
    )
    (net (code "135") (name "unconnected-(TP6-Pad0)") (class "Default")
      (node (ref "TP6") (pin "0") (pinfunction "0_0") (pintype "passive"))
    )
    (net (code "136") (name "unconnected-(U1-ATESTCK0-Pad165)") (class "Default")
      (node (ref "U1") (pin "165") (pinfunction "ATESTCK0_165") (pintype "passive+no_connect"))
    )
    (net (code "137") (name "unconnected-(U1-BUZZER{slash}DIS_LPD-Pad25)") (class "Default")
      (node (ref "U1") (pin "25") (pinfunction "BUZZER/DIS_LPD_25") (pintype "passive"))
    )
    (net (code "138") (name "unconnected-(U1-G0_GTXC{slash}RG0_TXCLK{slash}M0M_TXCLK{slash}M0P_RXCLK{slash}GPIO5-Pad122)") (class "Default")
      (node (ref "U1") (pin "122") (pinfunction "G0_GTXC/RG0_TXCLK/M0M_TXCLK/M0P_RXCLK/GPIO5_122") (pintype "passive"))
    )
    (net (code "139") (name "unconnected-(U1-G0_TXD6{slash}P1LED1{slash}SLED_P1_5A-Pad130)") (class "Default")
      (node (ref "U1") (pin "130") (pinfunction "G0_TXD6/P1LED1/SLED_P1_5A_130") (pintype "passive"))
    )
    (net (code "140") (name "unconnected-(U1-G1_TXD0{slash}RG1_TXD0{slash}M1M_TXD0{slash}M1P_RXD0-Pad86)") (class "Default")
      (node (ref "U1") (pin "86") (pinfunction "G1_TXD0/RG1_TXD0/M1M_TXD0/M1P_RXD0_86") (pintype "passive"))
    )
    (net (code "141") (name "unconnected-(U1-G1_TXD1{slash}RG1_TXD1{slash}M1M_TXD1{slash}M1P_RXD1-Pad85)") (class "Default")
      (node (ref "U1") (pin "85") (pinfunction "G1_TXD1/RG1_TXD1/M1M_TXD1/M1P_RXD1_85") (pintype "passive"))
    )
    (net (code "142") (name "unconnected-(U1-G1_TXD2{slash}RG1_TXD2{slash}M1M_TXD2{slash}M1P_RXD2-Pad84)") (class "Default")
      (node (ref "U1") (pin "84") (pinfunction "G1_TXD2/RG1_TXD2/M1M_TXD2/M1P_RXD2_84") (pintype "passive"))
    )
    (net (code "143") (name "unconnected-(U1-G1_TXD3{slash}RG1_TXD3{slash}M1M_TXD3{slash}M1P_RXD3-Pad83)") (class "Default")
      (node (ref "U1") (pin "83") (pinfunction "G1_TXD3/RG1_TXD3/M1M_TXD3/M1P_RXD3_83") (pintype "passive"))
    )
    (net (code "144") (name "unconnected-(U1-G1_TXD4{slash}P6LED2{slash}SPI_CS-Pad82)") (class "Default")
      (node (ref "U1") (pin "82") (pinfunction "G1_TXD4/P6LED2/SPI_CS_82") (pintype "passive"))
    )
    (net (code "145") (name "unconnected-(U1-G1_TXD5{slash}P7LED1{slash}SPI_D1-Pad81)") (class "Default")
      (node (ref "U1") (pin "81") (pinfunction "G1_TXD5/P7LED1/SPI_D1_81") (pintype "passive"))
    )
    (net (code "146") (name "unconnected-(U1-G1_TXD6{slash}P7LED0{slash}SPI_D0-Pad80)") (class "Default")
      (node (ref "U1") (pin "80") (pinfunction "G1_TXD6/P7LED0/SPI_D0_80") (pintype "passive"))
    )
    (net (code "147") (name "unconnected-(U1-G1_TXD7{slash}P7LED2{slash}SPI_CLK-Pad79)") (class "Default")
      (node (ref "U1") (pin "79") (pinfunction "G1_TXD7/P7LED2/SPI_CLK_79") (pintype "passive"))
    )
    (net (code "148") (name "unconnected-(U1-G1_TXEN{slash}RG1_TXCTL{slash}M1M_TXEN{slash}M1P_RXDV-Pad87)") (class "Default")
      (node (ref "U1") (pin "87") (pinfunction "G1_TXEN/RG1_TXCTL/M1M_TXEN/M1P_RXDV_87") (pintype "passive"))
    )
    (net (code "149") (name "unconnected-(U1-LED_DA{slash}P0LED1{slash}SLED_G2A-Pad134)") (class "Default")
      (node (ref "U1") (pin "134") (pinfunction "LED_DA/P0LED1/SLED_G2A_134") (pintype "passive"))
    )
    (net (code "150") (name "unconnected-(U1-RESERVED-Pad14)") (class "Default")
      (node (ref "U1") (pin "14") (pinfunction "RESERVED_14") (pintype "passive+no_connect"))
    )
    (net (code "151") (name "unconnected-(U1-RESERVED-Pad27)") (class "Default")
      (node (ref "U1") (pin "27") (pinfunction "RESERVED_27") (pintype "passive+no_connect"))
    )
    (net (code "152") (name "unconnected-(U1-RESERVED-Pad75)") (class "Default")
      (node (ref "U1") (pin "75") (pinfunction "RESERVED_75") (pintype "passive+no_connect"))
    )
    (net (code "153") (name "unconnected-(U1-RESERVED-Pad76)") (class "Default")
      (node (ref "U1") (pin "76") (pinfunction "RESERVED_76") (pintype "passive+no_connect"))
    )
    (net (code "154") (name "unconnected-(U1-RTT1-Pad18)") (class "Default")
      (node (ref "U1") (pin "18") (pinfunction "RTT1_18") (pintype "passive+no_connect"))
    )
    (net (code "155") (name "unconnected-(U1-RTT2-Pad19)") (class "Default")
      (node (ref "U1") (pin "19") (pinfunction "RTT2_19") (pintype "passive+no_connect"))
    )
  )
)
